# Main_Board.net
KiCad netlist of a schematic drawn in EAGLE
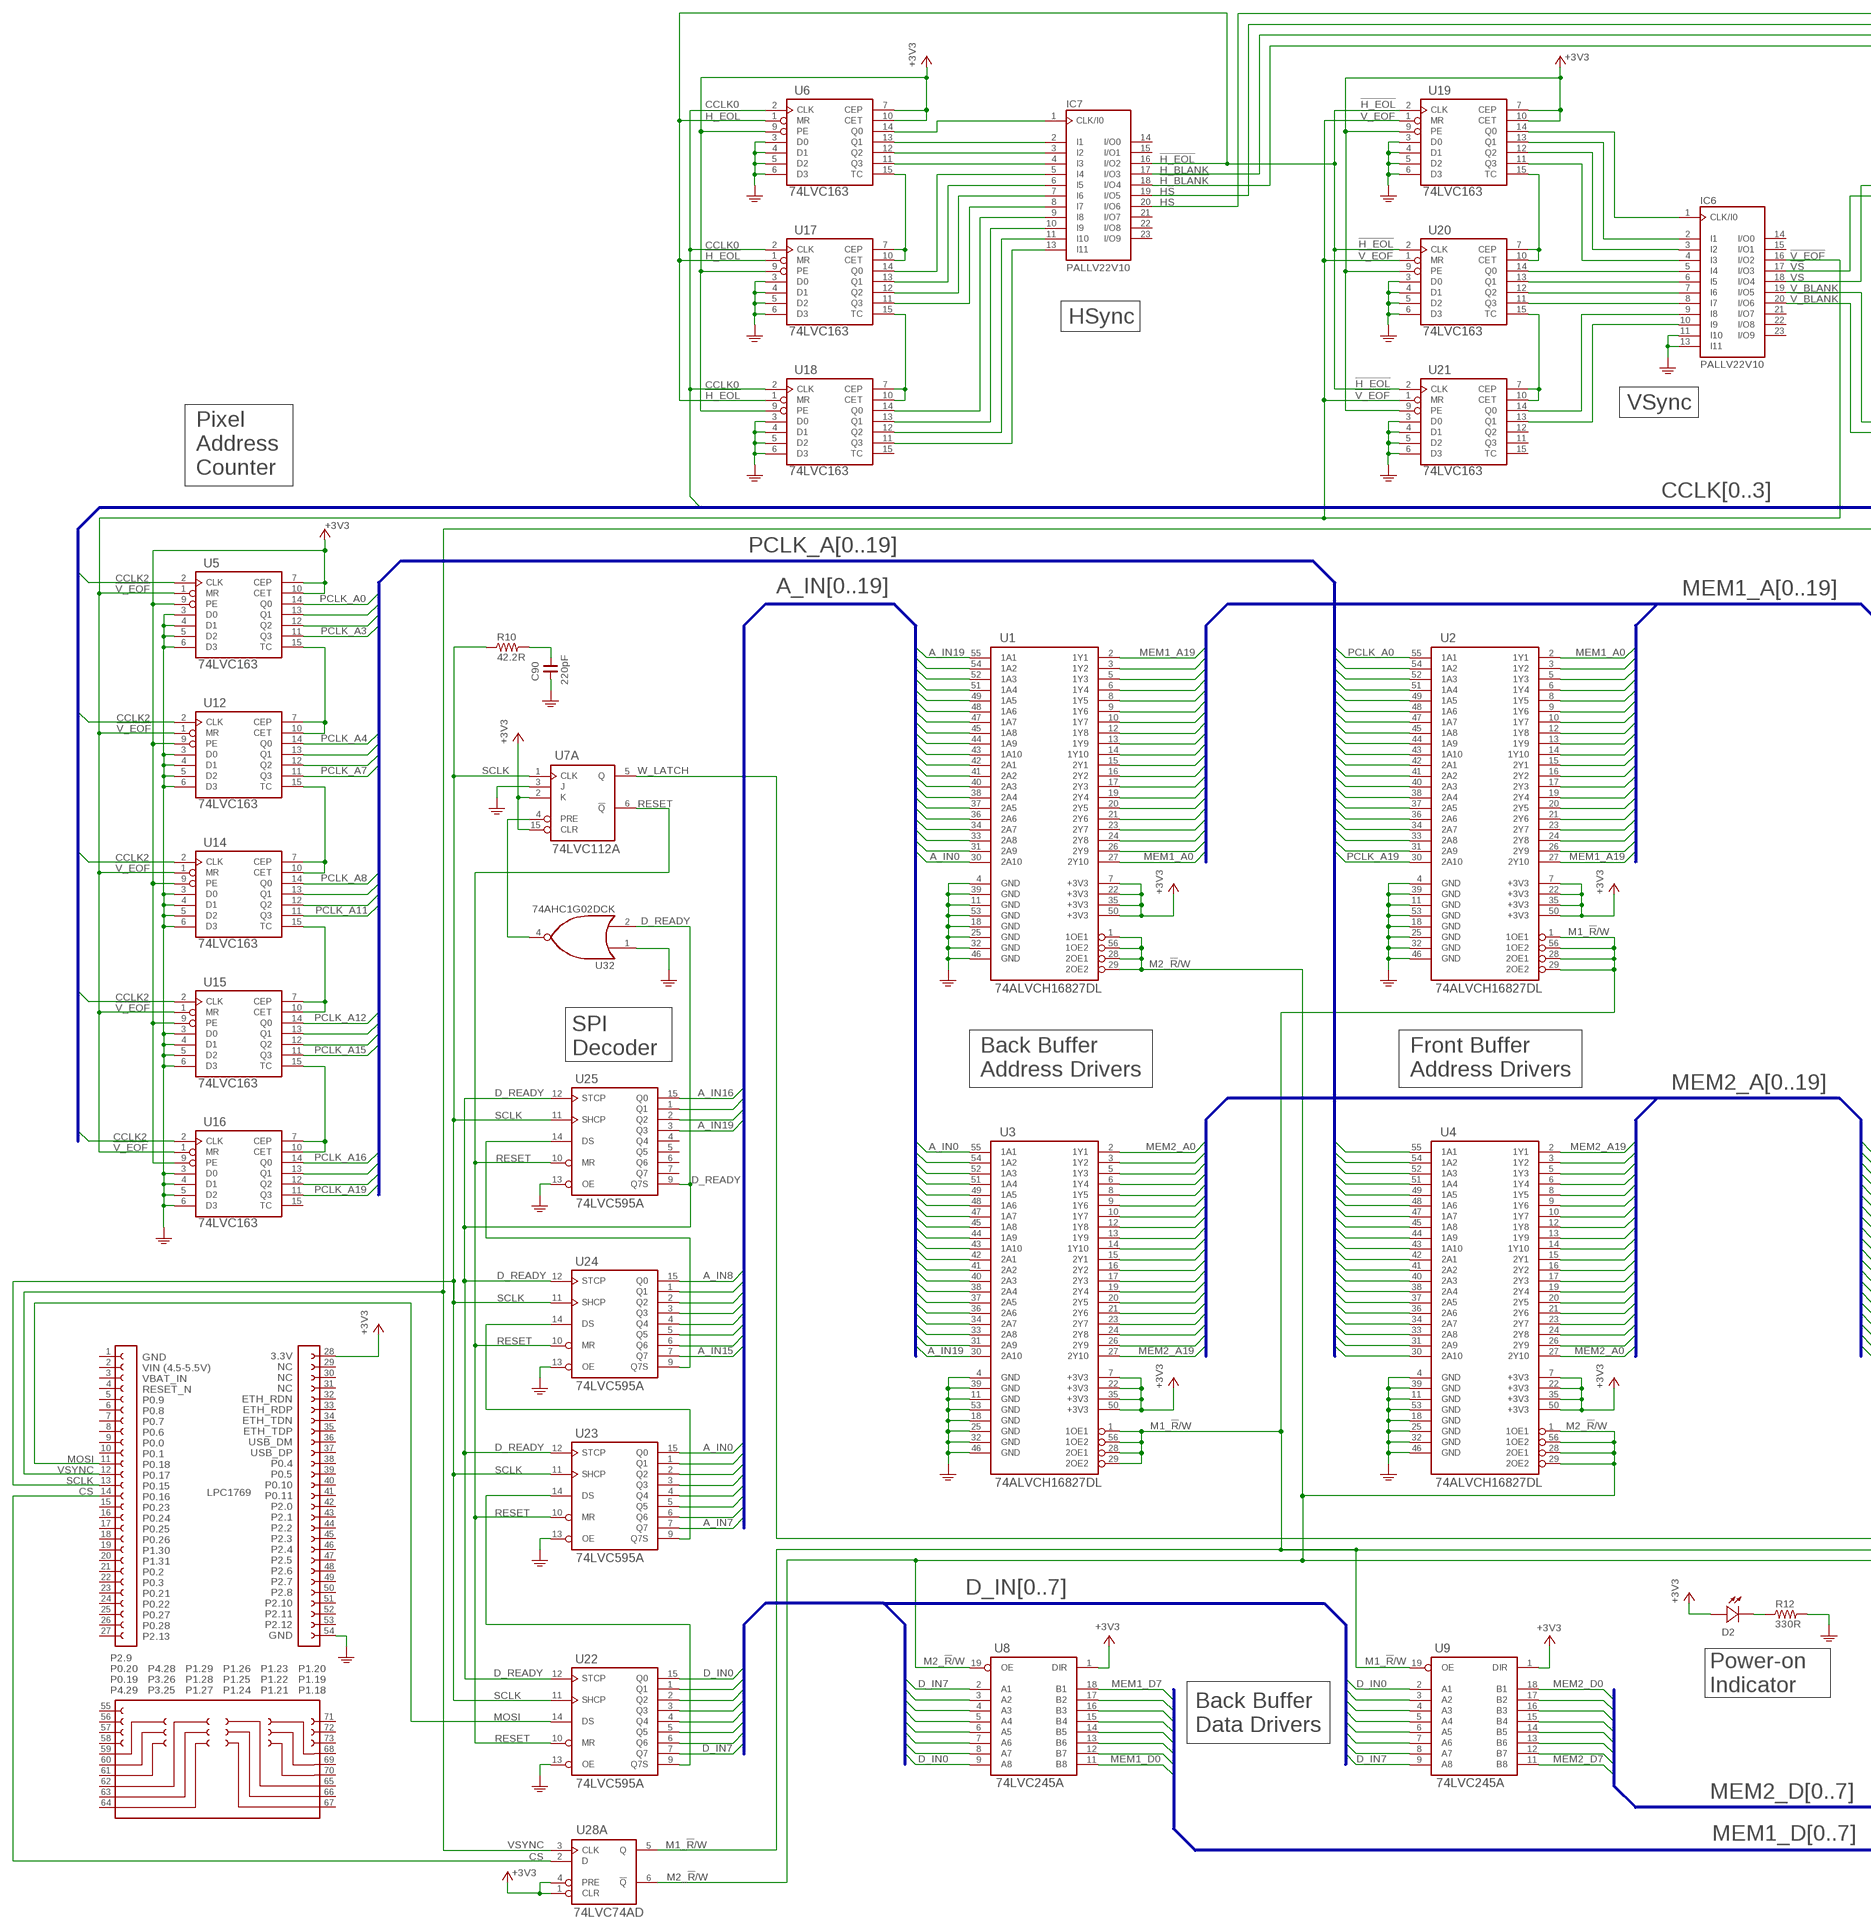
[diagram p0: schematic, sheet 1, part 1 of 2]
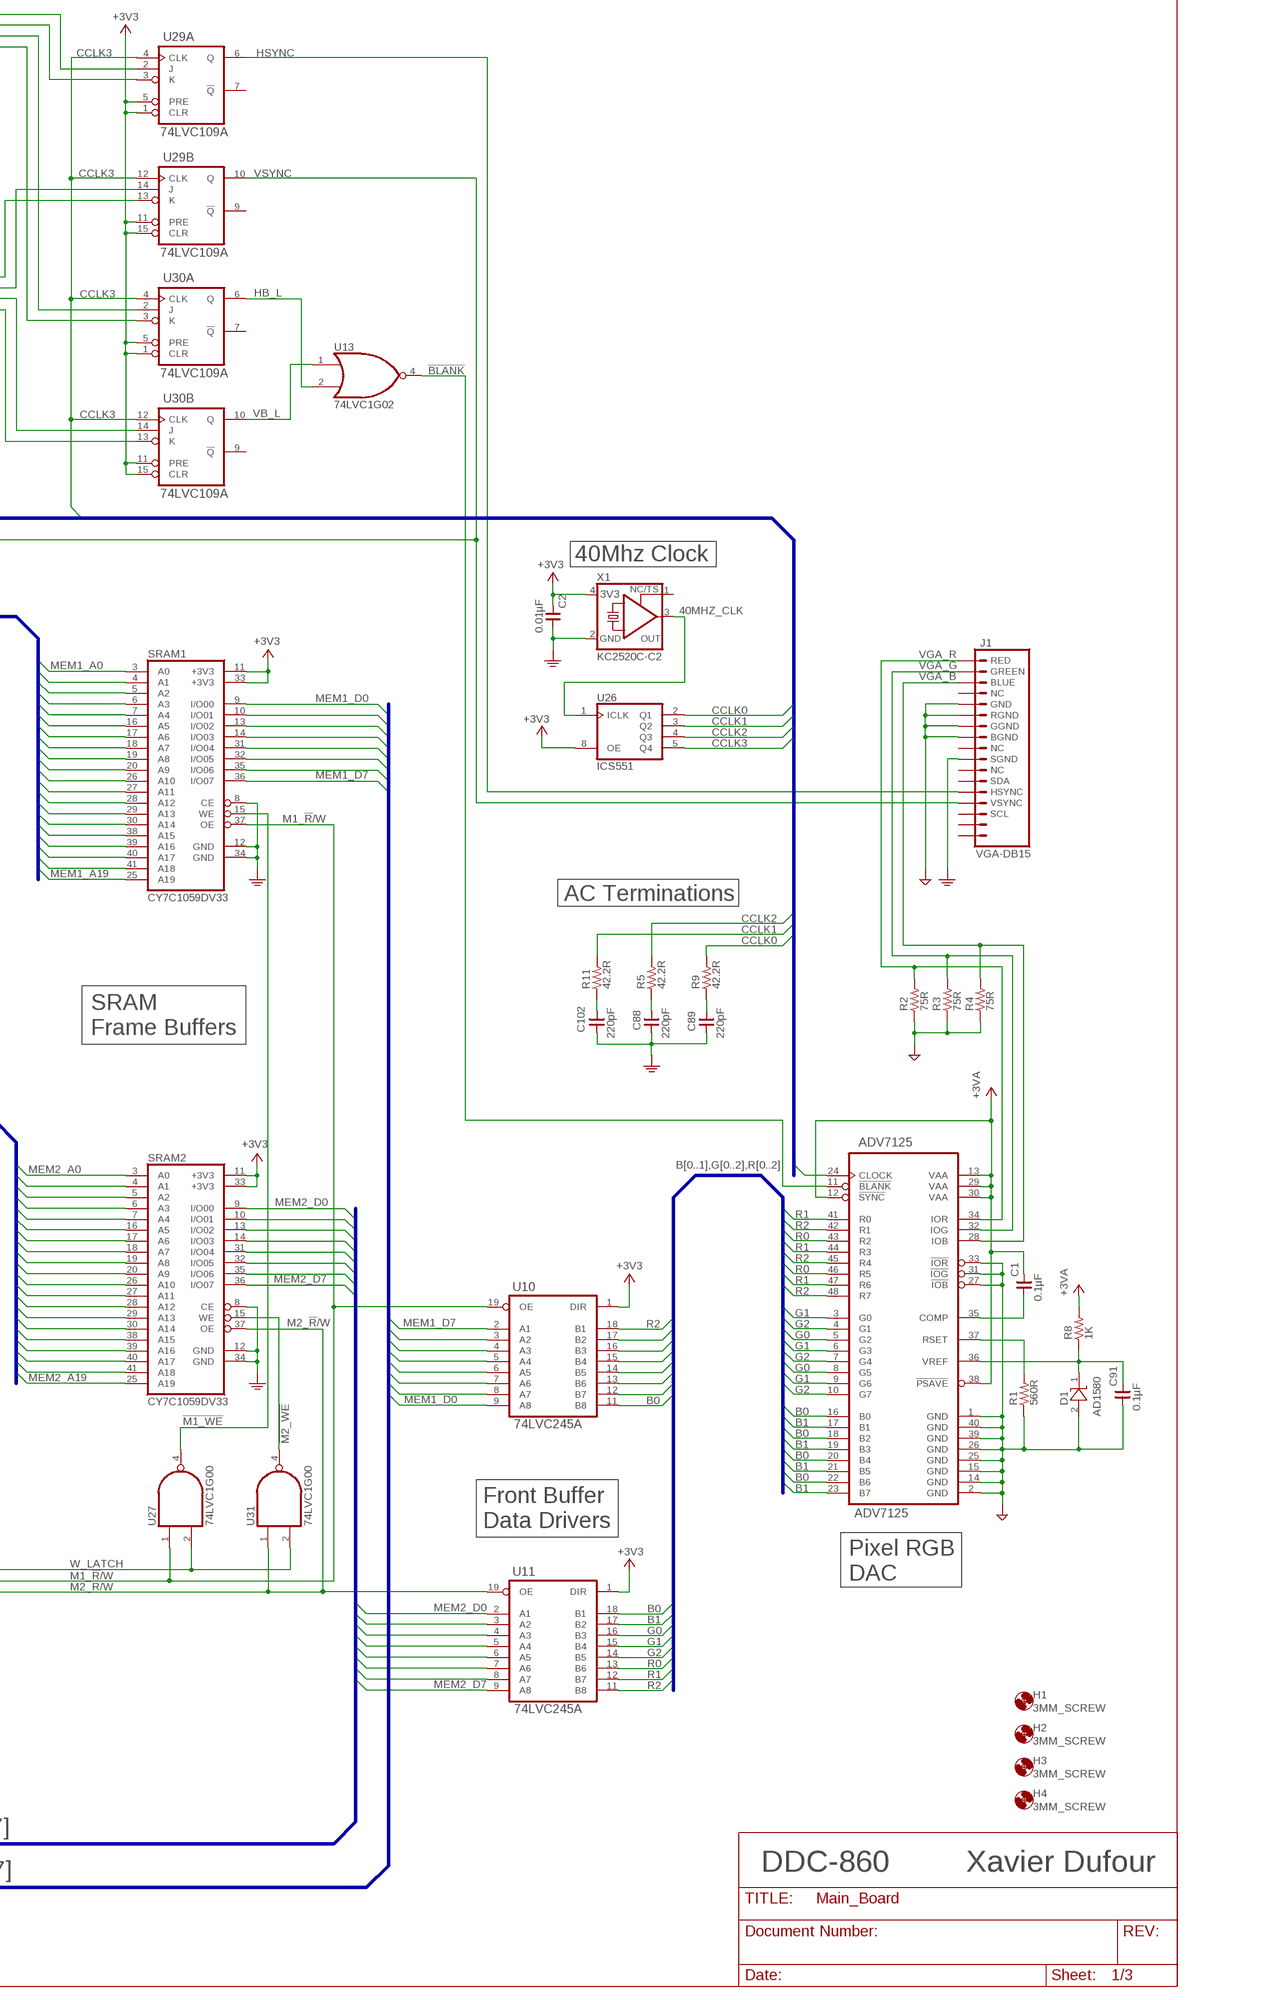
[diagram p1: schematic, sheet 1, part 2 of 2]
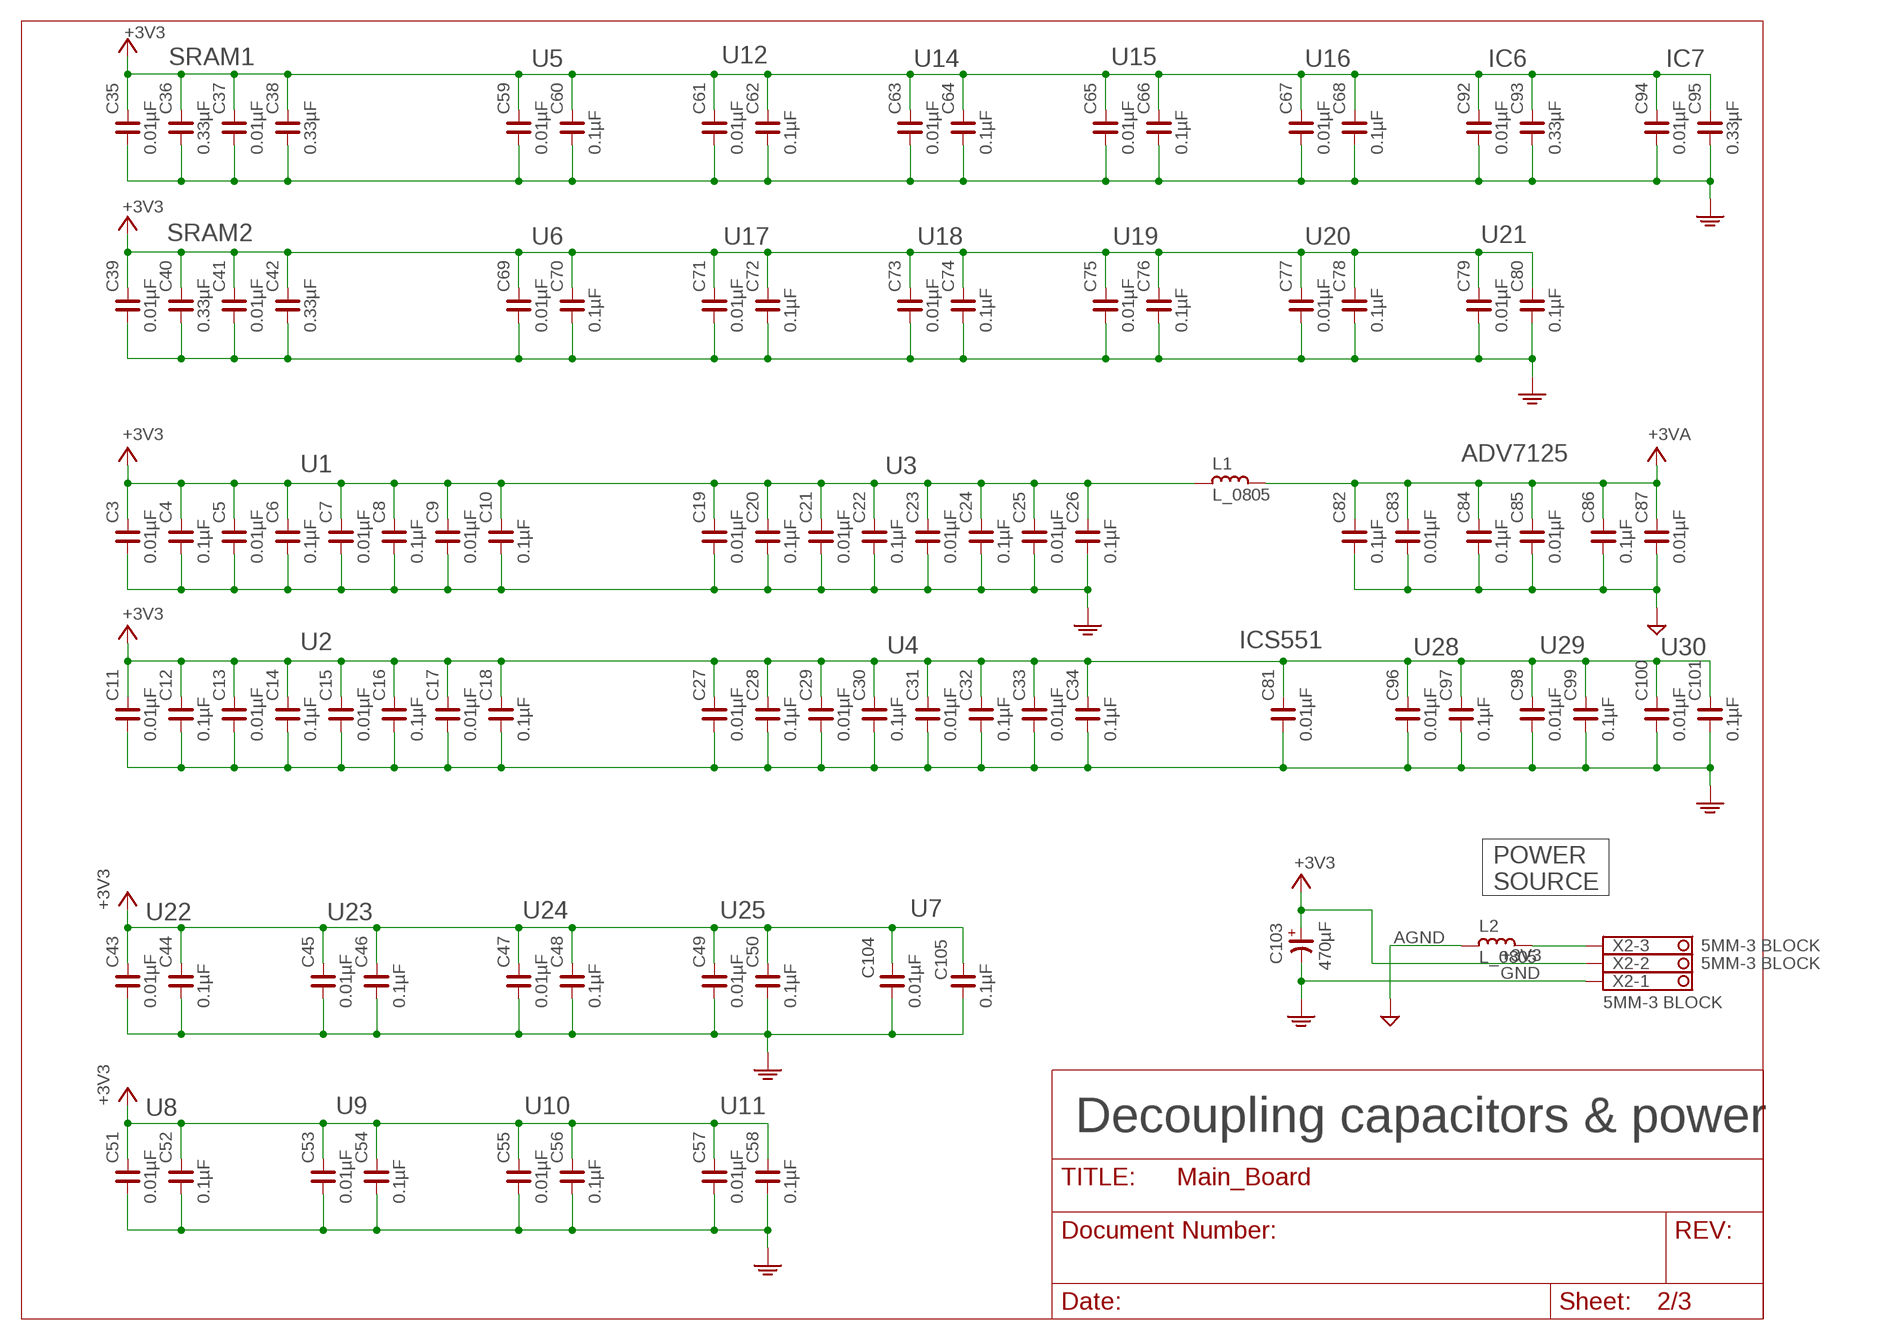
[diagram p2: schematic, sheet 2]
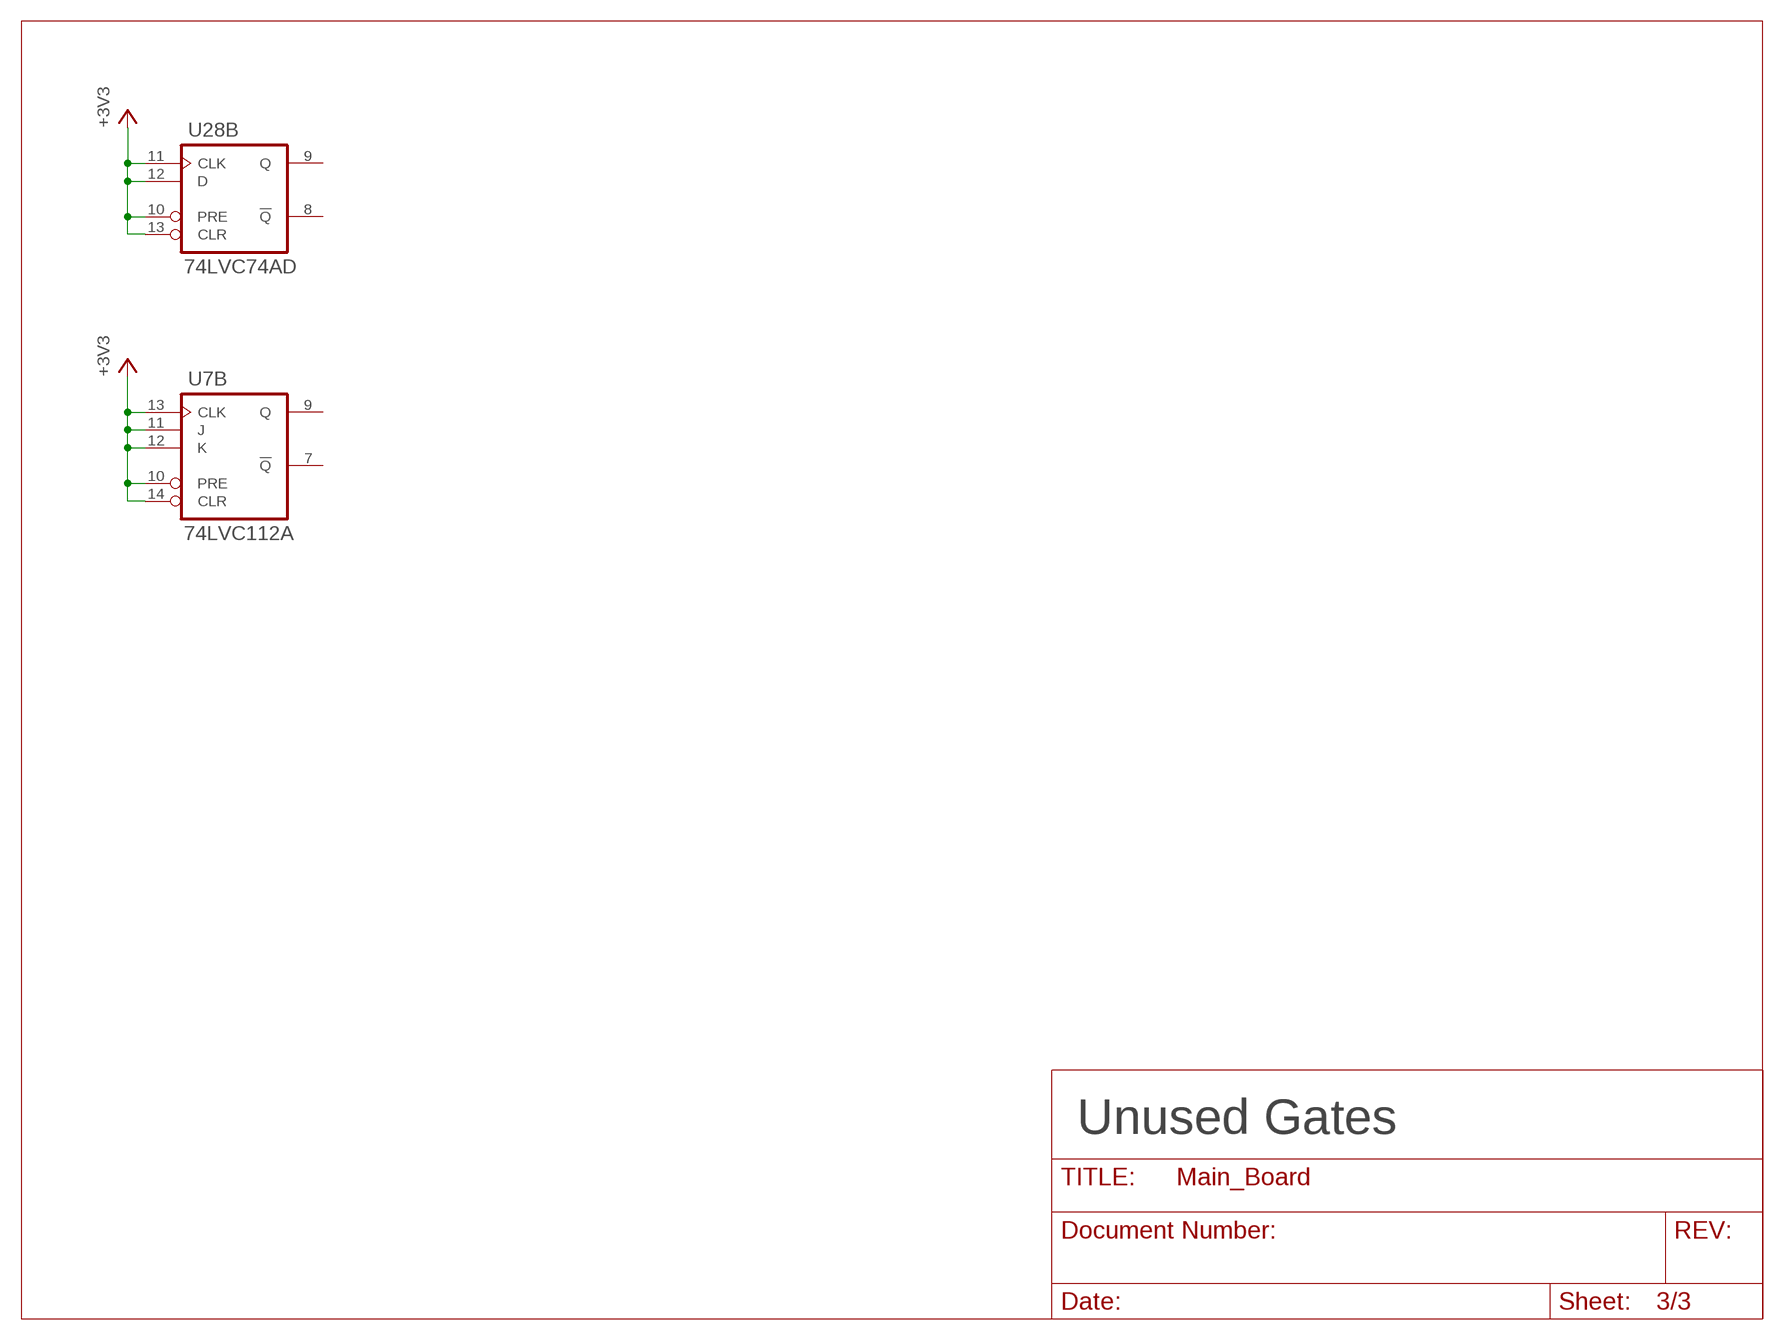
[diagram p3: schematic, sheet 3]

(export (version "E")
  (design (tool "Eeschema 10.0.6"))
  (components
    (comp (ref "C3")
      (value "0.01µF")
      (footprint "eagle-import:C0603")
      (libsource (lib "eagle-import") (part "C_0603"))
    )
    (comp (ref "C4")
      (value "0.1µF")
      (footprint "eagle-import:C0603")
      (libsource (lib "eagle-import") (part "C_0603"))
    )
    (comp (ref "C5")
      (value "0.01µF")
      (footprint "eagle-import:C0603")
      (libsource (lib "eagle-import") (part "C_0603"))
    )
    (comp (ref "C6")
      (value "0.1µF")
      (footprint "eagle-import:C0603")
      (libsource (lib "eagle-import") (part "C_0603"))
    )
    (comp (ref "C7")
      (value "0.01µF")
      (footprint "eagle-import:C0603")
      (libsource (lib "eagle-import") (part "C_0603"))
    )
    (comp (ref "C8")
      (value "0.1µF")
      (footprint "eagle-import:C0603")
      (libsource (lib "eagle-import") (part "C_0603"))
    )
    (comp (ref "C9")
      (value "0.01µF")
      (footprint "eagle-import:C0603")
      (libsource (lib "eagle-import") (part "C_0603"))
    )
    (comp (ref "C10")
      (value "0.1µF")
      (footprint "eagle-import:C0603")
      (libsource (lib "eagle-import") (part "C_0603"))
    )
    (comp (ref "C11")
      (value "0.01µF")
      (footprint "eagle-import:C0603")
      (libsource (lib "eagle-import") (part "C_0603"))
    )
    (comp (ref "C12")
      (value "0.1µF")
      (footprint "eagle-import:C0603")
      (libsource (lib "eagle-import") (part "C_0603"))
    )
    (comp (ref "C13")
      (value "0.01µF")
      (footprint "eagle-import:C0603")
      (libsource (lib "eagle-import") (part "C_0603"))
    )
    (comp (ref "C14")
      (value "0.1µF")
      (footprint "eagle-import:C0603")
      (libsource (lib "eagle-import") (part "C_0603"))
    )
    (comp (ref "C15")
      (value "0.01µF")
      (footprint "eagle-import:C0603")
      (libsource (lib "eagle-import") (part "C_0603"))
    )
    (comp (ref "C16")
      (value "0.1µF")
      (footprint "eagle-import:C0603")
      (libsource (lib "eagle-import") (part "C_0603"))
    )
    (comp (ref "C17")
      (value "0.01µF")
      (footprint "eagle-import:C0603")
      (libsource (lib "eagle-import") (part "C_0603"))
    )
    (comp (ref "C18")
      (value "0.1µF")
      (footprint "eagle-import:C0603")
      (libsource (lib "eagle-import") (part "C_0603"))
    )
    (comp (ref "C19")
      (value "0.01µF")
      (footprint "eagle-import:C0603")
      (libsource (lib "eagle-import") (part "C_0603"))
    )
    (comp (ref "C20")
      (value "0.1µF")
      (footprint "eagle-import:C0603")
      (libsource (lib "eagle-import") (part "C_0603"))
    )
    (comp (ref "C21")
      (value "0.01µF")
      (footprint "eagle-import:C0603")
      (libsource (lib "eagle-import") (part "C_0603"))
    )
    (comp (ref "C22")
      (value "0.1µF")
      (footprint "eagle-import:C0603")
      (libsource (lib "eagle-import") (part "C_0603"))
    )
    (comp (ref "C23")
      (value "0.01µF")
      (footprint "eagle-import:C0603")
      (libsource (lib "eagle-import") (part "C_0603"))
    )
    (comp (ref "C24")
      (value "0.1µF")
      (footprint "eagle-import:C0603")
      (libsource (lib "eagle-import") (part "C_0603"))
    )
    (comp (ref "C25")
      (value "0.01µF")
      (footprint "eagle-import:C0603")
      (libsource (lib "eagle-import") (part "C_0603"))
    )
    (comp (ref "C26")
      (value "0.1µF")
      (footprint "eagle-import:C0603")
      (libsource (lib "eagle-import") (part "C_0603"))
    )
    (comp (ref "C27")
      (value "0.01µF")
      (footprint "eagle-import:C0603")
      (libsource (lib "eagle-import") (part "C_0603"))
    )
    (comp (ref "C28")
      (value "0.1µF")
      (footprint "eagle-import:C0603")
      (libsource (lib "eagle-import") (part "C_0603"))
    )
    (comp (ref "C29")
      (value "0.01µF")
      (footprint "eagle-import:C0603")
      (libsource (lib "eagle-import") (part "C_0603"))
    )
    (comp (ref "C30")
      (value "0.1µF")
      (footprint "eagle-import:C0603")
      (libsource (lib "eagle-import") (part "C_0603"))
    )
    (comp (ref "C31")
      (value "0.01µF")
      (footprint "eagle-import:C0603")
      (libsource (lib "eagle-import") (part "C_0603"))
    )
    (comp (ref "C32")
      (value "0.1µF")
      (footprint "eagle-import:C0603")
      (libsource (lib "eagle-import") (part "C_0603"))
    )
    (comp (ref "C33")
      (value "0.01µF")
      (footprint "eagle-import:C0603")
      (libsource (lib "eagle-import") (part "C_0603"))
    )
    (comp (ref "C34")
      (value "0.1µF")
      (footprint "eagle-import:C0603")
      (libsource (lib "eagle-import") (part "C_0603"))
    )
    (comp (ref "C35")
      (value "0.01µF")
      (footprint "eagle-import:C0603")
      (libsource (lib "eagle-import") (part "C_0603"))
    )
    (comp (ref "C36")
      (value "0.33µF")
      (footprint "eagle-import:C0603")
      (libsource (lib "eagle-import") (part "C_0603"))
    )
    (comp (ref "C37")
      (value "0.01µF")
      (footprint "eagle-import:C0603")
      (libsource (lib "eagle-import") (part "C_0603"))
    )
    (comp (ref "C38")
      (value "0.33µF")
      (footprint "eagle-import:C0603")
      (libsource (lib "eagle-import") (part "C_0603"))
    )
    (comp (ref "C39")
      (value "0.01µF")
      (footprint "eagle-import:C0603")
      (libsource (lib "eagle-import") (part "C_0603"))
    )
    (comp (ref "C40")
      (value "0.33µF")
      (footprint "eagle-import:C0603")
      (libsource (lib "eagle-import") (part "C_0603"))
    )
    (comp (ref "C41")
      (value "0.01µF")
      (footprint "eagle-import:C0603")
      (libsource (lib "eagle-import") (part "C_0603"))
    )
    (comp (ref "C42")
      (value "0.33µF")
      (footprint "eagle-import:C0603")
      (libsource (lib "eagle-import") (part "C_0603"))
    )
    (comp (ref "C43")
      (value "0.01µF")
      (footprint "eagle-import:C0603")
      (libsource (lib "eagle-import") (part "C_0603"))
    )
    (comp (ref "C44")
      (value "0.1µF")
      (footprint "eagle-import:C0603")
      (libsource (lib "eagle-import") (part "C_0603"))
    )
    (comp (ref "C45")
      (value "0.01µF")
      (footprint "eagle-import:C0603")
      (libsource (lib "eagle-import") (part "C_0603"))
    )
    (comp (ref "C46")
      (value "0.1µF")
      (footprint "eagle-import:C0603")
      (libsource (lib "eagle-import") (part "C_0603"))
    )
    (comp (ref "C47")
      (value "0.01µF")
      (footprint "eagle-import:C0603")
      (fields (field (name "SPICEPREFIX") "C"))
      (libsource (lib "eagle-import") (part "C_0603"))
    )
    (comp (ref "C48")
      (value "0.1µF")
      (footprint "eagle-import:C0603")
      (libsource (lib "eagle-import") (part "C_0603"))
    )
    (comp (ref "C49")
      (value "0.01µF")
      (footprint "eagle-import:C0603")
      (libsource (lib "eagle-import") (part "C_0603"))
    )
    (comp (ref "C50")
      (value "0.1µF")
      (footprint "eagle-import:C0603")
      (libsource (lib "eagle-import") (part "C_0603"))
    )
    (comp (ref "C51")
      (value "0.01µF")
      (footprint "eagle-import:C0603")
      (libsource (lib "eagle-import") (part "C_0603"))
    )
    (comp (ref "C52")
      (value "0.1µF")
      (footprint "eagle-import:C0603")
      (libsource (lib "eagle-import") (part "C_0603"))
    )
    (comp (ref "C53")
      (value "0.01µF")
      (footprint "eagle-import:C0603")
      (libsource (lib "eagle-import") (part "C_0603"))
    )
    (comp (ref "C54")
      (value "0.1µF")
      (footprint "eagle-import:C0603")
      (libsource (lib "eagle-import") (part "C_0603"))
    )
    (comp (ref "C55")
      (value "0.01µF")
      (footprint "eagle-import:C0603")
      (libsource (lib "eagle-import") (part "C_0603"))
    )
    (comp (ref "C56")
      (value "0.1µF")
      (footprint "eagle-import:C0603")
      (libsource (lib "eagle-import") (part "C_0603"))
    )
    (comp (ref "C57")
      (value "0.01µF")
      (footprint "eagle-import:C0603")
      (libsource (lib "eagle-import") (part "C_0603"))
    )
    (comp (ref "C58")
      (value "0.1µF")
      (footprint "eagle-import:C0603")
      (libsource (lib "eagle-import") (part "C_0603"))
    )
    (comp (ref "C59")
      (value "0.01µF")
      (footprint "eagle-import:C0603")
      (libsource (lib "eagle-import") (part "C_0603"))
    )
    (comp (ref "C60")
      (value "0.1µF")
      (footprint "eagle-import:C0603")
      (libsource (lib "eagle-import") (part "C_0603"))
    )
    (comp (ref "C61")
      (value "0.01µF")
      (footprint "eagle-import:C0603")
      (libsource (lib "eagle-import") (part "C_0603"))
    )
    (comp (ref "C62")
      (value "0.1µF")
      (footprint "eagle-import:C0603")
      (libsource (lib "eagle-import") (part "C_0603"))
    )
    (comp (ref "C63")
      (value "0.01µF")
      (footprint "eagle-import:C0603")
      (libsource (lib "eagle-import") (part "C_0603"))
    )
    (comp (ref "C64")
      (value "0.1µF")
      (footprint "eagle-import:C0603")
      (libsource (lib "eagle-import") (part "C_0603"))
    )
    (comp (ref "C65")
      (value "0.01µF")
      (footprint "eagle-import:C0603")
      (libsource (lib "eagle-import") (part "C_0603"))
    )
    (comp (ref "C66")
      (value "0.1µF")
      (footprint "eagle-import:C0603")
      (libsource (lib "eagle-import") (part "C_0603"))
    )
    (comp (ref "C67")
      (value "0.01µF")
      (footprint "eagle-import:C0603")
      (libsource (lib "eagle-import") (part "C_0603"))
    )
    (comp (ref "C68")
      (value "0.1µF")
      (footprint "eagle-import:C0603")
      (libsource (lib "eagle-import") (part "C_0603"))
    )
    (comp (ref "C69")
      (value "0.01µF")
      (footprint "eagle-import:C0603")
      (libsource (lib "eagle-import") (part "C_0603"))
    )
    (comp (ref "C70")
      (value "0.1µF")
      (footprint "eagle-import:C0603")
      (libsource (lib "eagle-import") (part "C_0603"))
    )
    (comp (ref "C71")
      (value "0.01µF")
      (footprint "eagle-import:C0603")
      (libsource (lib "eagle-import") (part "C_0603"))
    )
    (comp (ref "C72")
      (value "0.1µF")
      (footprint "eagle-import:C0603")
      (libsource (lib "eagle-import") (part "C_0603"))
    )
    (comp (ref "C73")
      (value "0.01µF")
      (footprint "eagle-import:C0603")
      (libsource (lib "eagle-import") (part "C_0603"))
    )
    (comp (ref "C74")
      (value "0.1µF")
      (footprint "eagle-import:C0603")
      (libsource (lib "eagle-import") (part "C_0603"))
    )
    (comp (ref "C75")
      (value "0.01µF")
      (footprint "eagle-import:C0603")
      (libsource (lib "eagle-import") (part "C_0603"))
    )
    (comp (ref "C76")
      (value "0.1µF")
      (footprint "eagle-import:C0603")
      (libsource (lib "eagle-import") (part "C_0603"))
    )
    (comp (ref "C77")
      (value "0.01µF")
      (footprint "eagle-import:C0603")
      (libsource (lib "eagle-import") (part "C_0603"))
    )
    (comp (ref "C78")
      (value "0.1µF")
      (footprint "eagle-import:C0603")
      (libsource (lib "eagle-import") (part "C_0603"))
    )
    (comp (ref "C79")
      (value "0.01µF")
      (footprint "eagle-import:C0603")
      (libsource (lib "eagle-import") (part "C_0603"))
    )
    (comp (ref "C80")
      (value "0.1µF")
      (footprint "eagle-import:C0603")
      (libsource (lib "eagle-import") (part "C_0603"))
    )
    (comp (ref "C81")
      (value "0.01µF")
      (footprint "eagle-import:C0603")
      (libsource (lib "eagle-import") (part "C_0603"))
    )
    (comp (ref "C82")
      (value "0.1µF")
      (footprint "eagle-import:C0603")
      (libsource (lib "eagle-import") (part "C_0603"))
    )
    (comp (ref "C83")
      (value "0.01µF")
      (footprint "eagle-import:C0603")
      (libsource (lib "eagle-import") (part "C_0603"))
    )
    (comp (ref "C84")
      (value "0.1µF")
      (footprint "eagle-import:C0603")
      (libsource (lib "eagle-import") (part "C_0603"))
    )
    (comp (ref "C85")
      (value "0.01µF")
      (footprint "eagle-import:C0603")
      (libsource (lib "eagle-import") (part "C_0603"))
    )
    (comp (ref "C86")
      (value "0.1µF")
      (footprint "eagle-import:C0603")
      (libsource (lib "eagle-import") (part "C_0603"))
    )
    (comp (ref "C87")
      (value "0.01µF")
      (footprint "eagle-import:C0603")
      (libsource (lib "eagle-import") (part "C_0603"))
    )
    (comp (ref "C92")
      (value "0.01µF")
      (footprint "eagle-import:C0603")
      (libsource (lib "eagle-import") (part "C_0603"))
    )
    (comp (ref "C93")
      (value "0.33µF")
      (footprint "eagle-import:C0603")
      (libsource (lib "eagle-import") (part "C_0603"))
    )
    (comp (ref "C94")
      (value "0.01µF")
      (footprint "eagle-import:C0603")
      (libsource (lib "eagle-import") (part "C_0603"))
    )
    (comp (ref "C95")
      (value "0.33µF")
      (footprint "eagle-import:C0603")
      (libsource (lib "eagle-import") (part "C_0603"))
    )
    (comp (ref "C96")
      (value "0.01µF")
      (footprint "eagle-import:C0603")
      (libsource (lib "eagle-import") (part "C_0603"))
    )
    (comp (ref "C97")
      (value "0.1µF")
      (footprint "eagle-import:C0603")
      (libsource (lib "eagle-import") (part "C_0603"))
    )
    (comp (ref "C98")
      (value "0.01µF")
      (footprint "eagle-import:C0603")
      (libsource (lib "eagle-import") (part "C_0603"))
    )
    (comp (ref "C99")
      (value "0.1µF")
      (footprint "eagle-import:C0603")
      (libsource (lib "eagle-import") (part "C_0603"))
    )
    (comp (ref "C100")
      (value "0.01µF")
      (footprint "eagle-import:C0603")
      (libsource (lib "eagle-import") (part "C_0603"))
    )
    (comp (ref "C101")
      (value "0.1µF")
      (footprint "eagle-import:C0603")
      (libsource (lib "eagle-import") (part "C_0603"))
    )
    (comp (ref "C103")
      (value "470µF")
      (footprint "eagle-import:CSV-G")
      (libsource (lib "eagle-import") (part "CP_SV-G"))
    )
    (comp (ref "C104")
      (value "0.01µF")
      (footprint "eagle-import:C0603")
      (libsource (lib "eagle-import") (part "C_0603"))
    )
    (comp (ref "C105")
      (value "0.1µF")
      (footprint "eagle-import:C0603")
      (libsource (lib "eagle-import") (part "C_0603"))
    )
    (comp (ref "L1")
      (value "L_0805")
      (footprint "eagle-import:L0805")
      (libsource (lib "eagle-import") (part "L_0805"))
    )
    (comp (ref "L2")
      (value "L_0805")
      (footprint "eagle-import:L0805")
      (libsource (lib "eagle-import") (part "L_0805"))
    )
    (comp (ref "X2")
      (value "5MM-3 BLOCK")
      (footprint "eagle-import:TERMINAL-BLOCK-3-PIN-5MM")
      (libsource (lib "eagle-import") (part "TERMINAL-BLOCK-5MM-3-PIN-LONG-PAD"))
    )
    (comp (ref "U7")
      (value "74LVC112A")
      (footprint "eagle-import:SO16D(SOT109)")
      (libsource (lib "eagle-import") (part "74LVC112A"))
    )
    (comp (ref "U28")
      (value "74LVC74AD")
      (footprint "eagle-import:SO14(SOT108)")
      (libsource (lib "eagle-import") (part "74LVC74AD"))
    )
    (comp (ref "ADV7125")
      (value "ADV7125")
      (footprint "eagle-import:LQFP48(SOT313)")
      (libsource (lib "eagle-import") (part "ADV7125"))
    )
    (comp (ref "C1")
      (value "0.1µF")
      (footprint "eagle-import:C0603")
      (libsource (lib "eagle-import") (part "C_0603"))
    )
    (comp (ref "C2")
      (value "0.01µF")
      (footprint "eagle-import:C0603")
      (libsource (lib "eagle-import") (part "C_0603"))
    )
    (comp (ref "C88")
      (value "220pF")
      (footprint "eagle-import:C0603")
      (libsource (lib "eagle-import") (part "C_0603"))
    )
    (comp (ref "C89")
      (value "220pF")
      (footprint "eagle-import:C0603")
      (libsource (lib "eagle-import") (part "C_0603"))
    )
    (comp (ref "C90")
      (value "220pF")
      (footprint "eagle-import:C0603")
      (libsource (lib "eagle-import") (part "C_0603"))
    )
    (comp (ref "C91")
      (value "0.1µF")
      (footprint "eagle-import:C0603")
      (libsource (lib "eagle-import") (part "C_0603"))
    )
    (comp (ref "C102")
      (value "220pF")
      (footprint "eagle-import:C0603")
      (libsource (lib "eagle-import") (part "C_0603"))
    )
    (comp (ref "D1")
      (value "AD1580")
      (footprint "eagle-import:TO236-3(SOT23)")
      (fields (field (name "MPN") "AD1580BRTZ"))
      (libsource (lib "eagle-import") (part "AD1580"))
    )
    (comp (ref "D2")
      (value "DEL-1206")
      (footprint "eagle-import:DEL1206")
      (libsource (lib "eagle-import") (part "DEL-1206"))
    )
    (comp (ref "H1")
      (value "3MM_SCREW")
      (footprint "eagle-import:3MM_HOLE")
      (libsource (lib "eagle-import") (part "SCREW_MOUNT_HOLE3.0"))
    )
    (comp (ref "H2")
      (value "3MM_SCREW")
      (footprint "eagle-import:3MM_HOLE")
      (libsource (lib "eagle-import") (part "SCREW_MOUNT_HOLE3.0"))
    )
    (comp (ref "H3")
      (value "3MM_SCREW")
      (footprint "eagle-import:3MM_HOLE")
      (libsource (lib "eagle-import") (part "SCREW_MOUNT_HOLE3.0"))
    )
    (comp (ref "H4")
      (value "3MM_SCREW")
      (footprint "eagle-import:3MM_HOLE")
      (libsource (lib "eagle-import") (part "SCREW_MOUNT_HOLE3.0"))
    )
    (comp (ref "IC6")
      (value "PALLV22V10")
      (footprint "eagle-import:DIP24")
      (libsource (lib "eagle-import") (part "PALLV22V10"))
    )
    (comp (ref "IC7")
      (value "PALLV22V10")
      (footprint "eagle-import:DIP24")
      (libsource (lib "eagle-import") (part "PALLV22V10"))
    )
    (comp (ref "J1")
      (value "VGA-DB15")
      (footprint "eagle-import:DB15-VGA-90DEG")
      (libsource (lib "eagle-import") (part "VGA-DB15"))
    )
    (comp (ref "LPC1769")
      (value "LPCXPRESSO_LPC1769")
      (footprint "eagle-import:LPCXPRESSO_LPC1769")
      (libsource (lib "eagle-import") (part "LPCXPRESSO_LPC1769"))
    )
    (comp (ref "R1")
      (value "560R")
      (footprint "eagle-import:R0603")
      (libsource (lib "eagle-import") (part "R_0603"))
    )
    (comp (ref "R2")
      (value "75R")
      (footprint "eagle-import:R0603")
      (libsource (lib "eagle-import") (part "R_0603"))
    )
    (comp (ref "R3")
      (value "75R")
      (footprint "eagle-import:R0603")
      (libsource (lib "eagle-import") (part "R_0603"))
    )
    (comp (ref "R4")
      (value "75R")
      (footprint "eagle-import:R0603")
      (libsource (lib "eagle-import") (part "R_0603"))
    )
    (comp (ref "R5")
      (value "42.2R")
      (footprint "eagle-import:R0603")
      (libsource (lib "eagle-import") (part "R_0603"))
    )
    (comp (ref "R8")
      (value "1K")
      (footprint "eagle-import:R0603")
      (libsource (lib "eagle-import") (part "R_0603"))
    )
    (comp (ref "R9")
      (value "42.2R")
      (footprint "eagle-import:R0603")
      (libsource (lib "eagle-import") (part "R_0603"))
    )
    (comp (ref "R10")
      (value "42.2R")
      (footprint "eagle-import:R0603")
      (libsource (lib "eagle-import") (part "R_0603"))
    )
    (comp (ref "R11")
      (value "42.2R")
      (footprint "eagle-import:R0603")
      (libsource (lib "eagle-import") (part "R_0603"))
    )
    (comp (ref "R12")
      (value "330R")
      (footprint "eagle-import:R1206")
      (libsource (lib "eagle-import") (part "R_1206"))
    )
    (comp (ref "SRAM1")
      (value "CY7C1059DV33")
      (footprint "eagle-import:TSOPII-44")
      (libsource (lib "eagle-import") (part "CY7C1059DV33"))
    )
    (comp (ref "SRAM2")
      (value "CY7C1059DV33")
      (footprint "eagle-import:TSOPII-44")
      (libsource (lib "eagle-import") (part "CY7C1059DV33"))
    )
    (comp (ref "U1")
      (value "74ALVCH16827DL")
      (footprint "eagle-import:SSOP56(SOT371)")
      (libsource (lib "eagle-import") (part "74ALVCH16827DL"))
    )
    (comp (ref "U2")
      (value "74ALVCH16827DL")
      (footprint "eagle-import:SSOP56(SOT371)")
      (libsource (lib "eagle-import") (part "74ALVCH16827DL"))
    )
    (comp (ref "U3")
      (value "74ALVCH16827DL")
      (footprint "eagle-import:SSOP56(SOT371)")
      (libsource (lib "eagle-import") (part "74ALVCH16827DL"))
    )
    (comp (ref "U4")
      (value "74ALVCH16827DL")
      (footprint "eagle-import:SSOP56(SOT371)")
      (libsource (lib "eagle-import") (part "74ALVCH16827DL"))
    )
    (comp (ref "U5")
      (value "74LVC163")
      (footprint "eagle-import:SO16D(SOT109)")
      (libsource (lib "eagle-import") (part "74LVC163"))
    )
    (comp (ref "U6")
      (value "74LVC163")
      (footprint "eagle-import:SO16D(SOT109)")
      (libsource (lib "eagle-import") (part "74LVC163"))
    )
    (comp (ref "U8")
      (value "74LVC245A")
      (footprint "eagle-import:SO20DW(SOT163)")
      (libsource (lib "eagle-import") (part "74LVC245A"))
    )
    (comp (ref "U9")
      (value "74LVC245A")
      (footprint "eagle-import:SO20DW(SOT163)")
      (libsource (lib "eagle-import") (part "74LVC245A"))
    )
    (comp (ref "U10")
      (value "74LVC245A")
      (footprint "eagle-import:SO20DW(SOT163)")
      (libsource (lib "eagle-import") (part "74LVC245A"))
    )
    (comp (ref "U11")
      (value "74LVC245A")
      (footprint "eagle-import:SO20DW(SOT163)")
      (libsource (lib "eagle-import") (part "74LVC245A"))
    )
    (comp (ref "U12")
      (value "74LVC163")
      (footprint "eagle-import:SO16D(SOT109)")
      (libsource (lib "eagle-import") (part "74LVC163"))
    )
    (comp (ref "U13")
      (value "74LVC1G02")
      (footprint "eagle-import:SC70-5(SOT353)")
      (libsource (lib "eagle-import") (part "74LVC1G02"))
    )
    (comp (ref "U14")
      (value "74LVC163")
      (footprint "eagle-import:SO16D(SOT109)")
      (libsource (lib "eagle-import") (part "74LVC163"))
    )
    (comp (ref "U15")
      (value "74LVC163")
      (footprint "eagle-import:SO16D(SOT109)")
      (libsource (lib "eagle-import") (part "74LVC163"))
    )
    (comp (ref "U16")
      (value "74LVC163")
      (footprint "eagle-import:SO16D(SOT109)")
      (libsource (lib "eagle-import") (part "74LVC163"))
    )
    (comp (ref "U17")
      (value "74LVC163")
      (footprint "eagle-import:SO16D(SOT109)")
      (libsource (lib "eagle-import") (part "74LVC163"))
    )
    (comp (ref "U18")
      (value "74LVC163")
      (footprint "eagle-import:SO16D(SOT109)")
      (libsource (lib "eagle-import") (part "74LVC163"))
    )
    (comp (ref "U19")
      (value "74LVC163")
      (footprint "eagle-import:SO16D(SOT109)")
      (libsource (lib "eagle-import") (part "74LVC163"))
    )
    (comp (ref "U20")
      (value "74LVC163")
      (footprint "eagle-import:SO16D(SOT109)")
      (libsource (lib "eagle-import") (part "74LVC163"))
    )
    (comp (ref "U21")
      (value "74LVC163")
      (footprint "eagle-import:SO16D(SOT109)")
      (libsource (lib "eagle-import") (part "74LVC163"))
    )
    (comp (ref "U22")
      (value "74LVC595A")
      (footprint "eagle-import:SO16D(SOT109)")
      (libsource (lib "eagle-import") (part "74LVC595A"))
    )
    (comp (ref "U23")
      (value "74LVC595A")
      (footprint "eagle-import:SO16D(SOT109)")
      (libsource (lib "eagle-import") (part "74LVC595A"))
    )
    (comp (ref "U24")
      (value "74LVC595A")
      (footprint "eagle-import:SO16D(SOT109)")
      (libsource (lib "eagle-import") (part "74LVC595A"))
    )
    (comp (ref "U25")
      (value "74LVC595A")
      (footprint "eagle-import:SO16D(SOT109)")
      (libsource (lib "eagle-import") (part "74LVC595A"))
    )
    (comp (ref "U26")
      (value "ICS551")
      (footprint "eagle-import:SO08(SOT96)")
      (libsource (lib "eagle-import") (part "ICS551"))
    )
    (comp (ref "U27")
      (value "74LVC1G00")
      (footprint "eagle-import:SC70-5(SOT353)")
      (libsource (lib "eagle-import") (part "74LVC1G00"))
    )
    (comp (ref "U29")
      (value "74LVC109A")
      (footprint "eagle-import:SO16D(SOT109)")
      (libsource (lib "eagle-import") (part "74LVC109A"))
    )
    (comp (ref "U30")
      (value "74LVC109A")
      (footprint "eagle-import:SO16D(SOT109)")
      (libsource (lib "eagle-import") (part "74LVC109A"))
    )
    (comp (ref "U31")
      (value "74LVC1G00")
      (footprint "eagle-import:SC70-5(SOT353)")
      (libsource (lib "eagle-import") (part "74LVC1G00"))
    )
    (comp (ref "U32")
      (value "74AHC1G02DCK")
      (footprint "eagle-import:SC70-5(SOT353)")
      (libsource (lib "eagle-import") (part "74AHC1G02DCKSC70-5"))
    )
    (comp (ref "X1")
      (value "KC2520C-C2")
      (footprint "eagle-import:OSCXO2.5X2.0")
      (libsource (lib "eagle-import") (part "KC2520C-C2"))
    )
  )
  (nets
    (net (code "1") (name "+3V3") (class "Default")
      (node (ref "C10") (pin "2") (pinfunction "2_2") (pintype "passive"))
      (node (ref "C100") (pin "2") (pinfunction "2_2") (pintype "passive"))
      (node (ref "C101") (pin "2") (pinfunction "2_2") (pintype "passive"))
      (node (ref "C103") (pin "+") (pinfunction "+_+") (pintype "passive"))
      (node (ref "C104") (pin "2") (pinfunction "2_2") (pintype "passive"))
      (node (ref "C105") (pin "2") (pinfunction "2_2") (pintype "passive"))
      (node (ref "C11") (pin "2") (pinfunction "2_2") (pintype "passive"))
      (node (ref "C12") (pin "2") (pinfunction "2_2") (pintype "passive"))
      (node (ref "C13") (pin "2") (pinfunction "2_2") (pintype "passive"))
      (node (ref "C14") (pin "2") (pinfunction "2_2") (pintype "passive"))
      (node (ref "C15") (pin "2") (pinfunction "2_2") (pintype "passive"))
      (node (ref "C16") (pin "2") (pinfunction "2_2") (pintype "passive"))
      (node (ref "C17") (pin "2") (pinfunction "2_2") (pintype "passive"))
      (node (ref "C18") (pin "2") (pinfunction "2_2") (pintype "passive"))
      (node (ref "C19") (pin "2") (pinfunction "2_2") (pintype "passive"))
      (node (ref "C2") (pin "2") (pinfunction "2_2") (pintype "passive"))
      (node (ref "C20") (pin "2") (pinfunction "2_2") (pintype "passive"))
      (node (ref "C21") (pin "2") (pinfunction "2_2") (pintype "passive"))
      (node (ref "C22") (pin "2") (pinfunction "2_2") (pintype "passive"))
      (node (ref "C23") (pin "2") (pinfunction "2_2") (pintype "passive"))
      (node (ref "C24") (pin "2") (pinfunction "2_2") (pintype "passive"))
      (node (ref "C25") (pin "2") (pinfunction "2_2") (pintype "passive"))
      (node (ref "C26") (pin "2") (pinfunction "2_2") (pintype "passive"))
      (node (ref "C27") (pin "2") (pinfunction "2_2") (pintype "passive"))
      (node (ref "C28") (pin "2") (pinfunction "2_2") (pintype "passive"))
      (node (ref "C29") (pin "2") (pinfunction "2_2") (pintype "passive"))
      (node (ref "C3") (pin "2") (pinfunction "2_2") (pintype "passive"))
      (node (ref "C30") (pin "2") (pinfunction "2_2") (pintype "passive"))
      (node (ref "C31") (pin "2") (pinfunction "2_2") (pintype "passive"))
      (node (ref "C32") (pin "2") (pinfunction "2_2") (pintype "passive"))
      (node (ref "C33") (pin "2") (pinfunction "2_2") (pintype "passive"))
      (node (ref "C34") (pin "2") (pinfunction "2_2") (pintype "passive"))
      (node (ref "C35") (pin "2") (pinfunction "2_2") (pintype "passive"))
      (node (ref "C36") (pin "2") (pinfunction "2_2") (pintype "passive"))
      (node (ref "C37") (pin "2") (pinfunction "2_2") (pintype "passive"))
      (node (ref "C38") (pin "2") (pinfunction "2_2") (pintype "passive"))
      (node (ref "C39") (pin "2") (pinfunction "2_2") (pintype "passive"))
      (node (ref "C4") (pin "2") (pinfunction "2_2") (pintype "passive"))
      (node (ref "C40") (pin "2") (pinfunction "2_2") (pintype "passive"))
      (node (ref "C41") (pin "2") (pinfunction "2_2") (pintype "passive"))
      (node (ref "C42") (pin "2") (pinfunction "2_2") (pintype "passive"))
      (node (ref "C43") (pin "2") (pinfunction "2_2") (pintype "passive"))
      (node (ref "C44") (pin "2") (pinfunction "2_2") (pintype "passive"))
      (node (ref "C45") (pin "2") (pinfunction "2_2") (pintype "passive"))
      (node (ref "C46") (pin "2") (pinfunction "2_2") (pintype "passive"))
      (node (ref "C47") (pin "2") (pinfunction "2_2") (pintype "passive"))
      (node (ref "C48") (pin "2") (pinfunction "2_2") (pintype "passive"))
      (node (ref "C49") (pin "2") (pinfunction "2_2") (pintype "passive"))
      (node (ref "C5") (pin "2") (pinfunction "2_2") (pintype "passive"))
      (node (ref "C50") (pin "2") (pinfunction "2_2") (pintype "passive"))
      (node (ref "C51") (pin "2") (pinfunction "2_2") (pintype "passive"))
      (node (ref "C52") (pin "2") (pinfunction "2_2") (pintype "passive"))
      (node (ref "C53") (pin "2") (pinfunction "2_2") (pintype "passive"))
      (node (ref "C54") (pin "2") (pinfunction "2_2") (pintype "passive"))
      (node (ref "C55") (pin "2") (pinfunction "2_2") (pintype "passive"))
      (node (ref "C56") (pin "2") (pinfunction "2_2") (pintype "passive"))
      (node (ref "C57") (pin "2") (pinfunction "2_2") (pintype "passive"))
      (node (ref "C58") (pin "2") (pinfunction "2_2") (pintype "passive"))
      (node (ref "C59") (pin "2") (pinfunction "2_2") (pintype "passive"))
      (node (ref "C6") (pin "2") (pinfunction "2_2") (pintype "passive"))
      (node (ref "C60") (pin "2") (pinfunction "2_2") (pintype "passive"))
      (node (ref "C61") (pin "2") (pinfunction "2_2") (pintype "passive"))
      (node (ref "C62") (pin "2") (pinfunction "2_2") (pintype "passive"))
      (node (ref "C63") (pin "2") (pinfunction "2_2") (pintype "passive"))
      (node (ref "C64") (pin "2") (pinfunction "2_2") (pintype "passive"))
      (node (ref "C65") (pin "2") (pinfunction "2_2") (pintype "passive"))
      (node (ref "C66") (pin "2") (pinfunction "2_2") (pintype "passive"))
      (node (ref "C67") (pin "2") (pinfunction "2_2") (pintype "passive"))
      (node (ref "C68") (pin "2") (pinfunction "2_2") (pintype "passive"))
      (node (ref "C69") (pin "2") (pinfunction "2_2") (pintype "passive"))
      (node (ref "C7") (pin "2") (pinfunction "2_2") (pintype "passive"))
      (node (ref "C70") (pin "2") (pinfunction "2_2") (pintype "passive"))
      (node (ref "C71") (pin "2") (pinfunction "2_2") (pintype "passive"))
      (node (ref "C72") (pin "2") (pinfunction "2_2") (pintype "passive"))
      (node (ref "C73") (pin "2") (pinfunction "2_2") (pintype "passive"))
      (node (ref "C74") (pin "2") (pinfunction "2_2") (pintype "passive"))
      (node (ref "C75") (pin "2") (pinfunction "2_2") (pintype "passive"))
      (node (ref "C76") (pin "2") (pinfunction "2_2") (pintype "passive"))
      (node (ref "C77") (pin "2") (pinfunction "2_2") (pintype "passive"))
      (node (ref "C78") (pin "2") (pinfunction "2_2") (pintype "passive"))
      (node (ref "C79") (pin "2") (pinfunction "2_2") (pintype "passive"))
      (node (ref "C8") (pin "2") (pinfunction "2_2") (pintype "passive"))
      (node (ref "C80") (pin "2") (pinfunction "2_2") (pintype "passive"))
      (node (ref "C81") (pin "2") (pinfunction "2_2") (pintype "passive"))
      (node (ref "C9") (pin "2") (pinfunction "2_2") (pintype "passive"))
      (node (ref "C92") (pin "2") (pinfunction "2_2") (pintype "passive"))
      (node (ref "C93") (pin "2") (pinfunction "2_2") (pintype "passive"))
      (node (ref "C94") (pin "2") (pinfunction "2_2") (pintype "passive"))
      (node (ref "C95") (pin "2") (pinfunction "2_2") (pintype "passive"))
      (node (ref "C96") (pin "2") (pinfunction "2_2") (pintype "passive"))
      (node (ref "C97") (pin "2") (pinfunction "2_2") (pintype "passive"))
      (node (ref "C98") (pin "2") (pinfunction "2_2") (pintype "passive"))
      (node (ref "C99") (pin "2") (pinfunction "2_2") (pintype "passive"))
      (node (ref "D2") (pin "A") (pinfunction "A_A") (pintype "passive"))
      (node (ref "L1") (pin "2") (pinfunction "2_2") (pintype "passive"))
      (node (ref "LPC1769") (pin "28") (pinfunction "28_28") (pintype "passive"))
      (node (ref "SRAM1") (pin "11") (pinfunction "+3V3_11") (pintype "power_in"))
      (node (ref "SRAM1") (pin "33") (pinfunction "+3V3_33") (pintype "power_in"))
      (node (ref "SRAM2") (pin "11") (pinfunction "+3V3_11") (pintype "power_in"))
      (node (ref "SRAM2") (pin "33") (pinfunction "+3V3_33") (pintype "power_in"))
      (node (ref "U1") (pin "22") (pinfunction "+3V3_22") (pintype "power_in"))
      (node (ref "U1") (pin "35") (pinfunction "+3V3_35") (pintype "power_in"))
      (node (ref "U1") (pin "50") (pinfunction "+3V3_50") (pintype "power_in"))
      (node (ref "U1") (pin "7") (pinfunction "+3V3_7") (pintype "power_in"))
      (node (ref "U10") (pin "1") (pinfunction "DIR_1") (pintype "input"))
      (node (ref "U11") (pin "1") (pinfunction "DIR_1") (pintype "input"))
      (node (ref "U12") (pin "9") (pinfunction "PE_9") (pintype "input"))
      (node (ref "U14") (pin "9") (pinfunction "PE_9") (pintype "input"))
      (node (ref "U15") (pin "9") (pinfunction "PE_9") (pintype "input"))
      (node (ref "U16") (pin "9") (pinfunction "PE_9") (pintype "input"))
      (node (ref "U17") (pin "9") (pinfunction "PE_9") (pintype "input"))
      (node (ref "U18") (pin "9") (pinfunction "PE_9") (pintype "input"))
      (node (ref "U19") (pin "10") (pinfunction "CET_10") (pintype "input"))
      (node (ref "U19") (pin "7") (pinfunction "CEP_7") (pintype "input"))
      (node (ref "U19") (pin "9") (pinfunction "PE_9") (pintype "input"))
      (node (ref "U2") (pin "22") (pinfunction "+3V3_22") (pintype "power_in"))
      (node (ref "U2") (pin "35") (pinfunction "+3V3_35") (pintype "power_in"))
      (node (ref "U2") (pin "50") (pinfunction "+3V3_50") (pintype "power_in"))
      (node (ref "U2") (pin "7") (pinfunction "+3V3_7") (pintype "power_in"))
      (node (ref "U20") (pin "9") (pinfunction "PE_9") (pintype "input"))
      (node (ref "U21") (pin "9") (pinfunction "PE_9") (pintype "input"))
      (node (ref "U26") (pin "8") (pinfunction "OE_8") (pintype "input"))
      (node (ref "U28") (pin "1") (pinfunction "CLR_1") (pintype "input"))
      (node (ref "U28") (pin "10") (pinfunction "PRE_10") (pintype "input"))
      (node (ref "U28") (pin "11") (pinfunction "CLK_11") (pintype "input"))
      (node (ref "U28") (pin "12") (pinfunction "D_12") (pintype "input"))
      (node (ref "U28") (pin "13") (pinfunction "CLR_13") (pintype "input"))
      (node (ref "U28") (pin "4") (pinfunction "PRE_4") (pintype "input"))
      (node (ref "U29") (pin "1") (pinfunction "CLR_1") (pintype "input"))
      (node (ref "U29") (pin "11") (pinfunction "PRE_11") (pintype "input"))
      (node (ref "U29") (pin "15") (pinfunction "CLR_15") (pintype "input"))
      (node (ref "U29") (pin "5") (pinfunction "PRE_5") (pintype "input"))
      (node (ref "U3") (pin "22") (pinfunction "+3V3_22") (pintype "power_in"))
      (node (ref "U3") (pin "35") (pinfunction "+3V3_35") (pintype "power_in"))
      (node (ref "U3") (pin "50") (pinfunction "+3V3_50") (pintype "power_in"))
      (node (ref "U3") (pin "7") (pinfunction "+3V3_7") (pintype "power_in"))
      (node (ref "U30") (pin "1") (pinfunction "CLR_1") (pintype "input"))
      (node (ref "U30") (pin "11") (pinfunction "PRE_11") (pintype "input"))
      (node (ref "U30") (pin "15") (pinfunction "CLR_15") (pintype "input"))
      (node (ref "U30") (pin "5") (pinfunction "PRE_5") (pintype "input"))
      (node (ref "U4") (pin "22") (pinfunction "+3V3_22") (pintype "power_in"))
      (node (ref "U4") (pin "35") (pinfunction "+3V3_35") (pintype "power_in"))
      (node (ref "U4") (pin "50") (pinfunction "+3V3_50") (pintype "power_in"))
      (node (ref "U4") (pin "7") (pinfunction "+3V3_7") (pintype "power_in"))
      (node (ref "U5") (pin "10") (pinfunction "CET_10") (pintype "input"))
      (node (ref "U5") (pin "7") (pinfunction "CEP_7") (pintype "input"))
      (node (ref "U5") (pin "9") (pinfunction "PE_9") (pintype "input"))
      (node (ref "U6") (pin "10") (pinfunction "CET_10") (pintype "input"))
      (node (ref "U6") (pin "7") (pinfunction "CEP_7") (pintype "input"))
      (node (ref "U6") (pin "9") (pinfunction "PE_9") (pintype "input"))
      (node (ref "U7") (pin "10") (pinfunction "PRE_10") (pintype "input"))
      (node (ref "U7") (pin "11") (pinfunction "J_11") (pintype "input"))
      (node (ref "U7") (pin "12") (pinfunction "K_12") (pintype "input"))
      (node (ref "U7") (pin "13") (pinfunction "CLK_13") (pintype "input"))
      (node (ref "U7") (pin "14") (pinfunction "CLR_14") (pintype "input"))
      (node (ref "U7") (pin "15") (pinfunction "CLR_15") (pintype "input"))
      (node (ref "U7") (pin "2") (pinfunction "K_2") (pintype "input"))
      (node (ref "U8") (pin "1") (pinfunction "DIR_1") (pintype "input"))
      (node (ref "U9") (pin "1") (pinfunction "DIR_1") (pintype "input"))
      (node (ref "X1") (pin "4") (pinfunction "+3V3_4") (pintype "power_in"))
      (node (ref "X2") (pin "2") (pinfunction "K_2") (pintype "passive"))
    )
    (net (code "2") (name "+3VA") (class "Default")
      (node (ref "ADV7125") (pin "12") (pinfunction "~{SYNC}_12") (pintype "input"))
      (node (ref "ADV7125") (pin "13") (pinfunction "VAA_13") (pintype "power_in"))
      (node (ref "ADV7125") (pin "29") (pinfunction "VAA_29") (pintype "power_in"))
      (node (ref "ADV7125") (pin "30") (pinfunction "VAA_30") (pintype "power_in"))
      (node (ref "ADV7125") (pin "38") (pinfunction "~{PSAVE}_38") (pintype "input"))
      (node (ref "C1") (pin "2") (pinfunction "2_2") (pintype "passive"))
      (node (ref "C82") (pin "2") (pinfunction "2_2") (pintype "passive"))
      (node (ref "C83") (pin "2") (pinfunction "2_2") (pintype "passive"))
      (node (ref "C84") (pin "2") (pinfunction "2_2") (pintype "passive"))
      (node (ref "C85") (pin "2") (pinfunction "2_2") (pintype "passive"))
      (node (ref "C86") (pin "2") (pinfunction "2_2") (pintype "passive"))
      (node (ref "C87") (pin "2") (pinfunction "2_2") (pintype "passive"))
      (node (ref "L1") (pin "1") (pinfunction "1_1") (pintype "passive"))
      (node (ref "R8") (pin "2") (pinfunction "2_2") (pintype "passive"))
    )
    (net (code "12") (name "40MHZ_CLK") (class "Default")
      (node (ref "U26") (pin "1") (pinfunction "ICLK_1") (pintype "input"))
      (node (ref "X1") (pin "3") (pinfunction "OUT_3") (pintype "output"))
    )
    (net (code "13") (name "AGND") (class "Default")
      (node (ref "ADV7125") (pin "1") (pinfunction "GND_1") (pintype "passive"))
      (node (ref "ADV7125") (pin "14") (pinfunction "GND_14") (pintype "passive"))
      (node (ref "ADV7125") (pin "15") (pinfunction "GND_15") (pintype "passive"))
      (node (ref "ADV7125") (pin "2") (pinfunction "GND_2") (pintype "passive"))
      (node (ref "ADV7125") (pin "25") (pinfunction "GND_25") (pintype "passive"))
      (node (ref "ADV7125") (pin "26") (pinfunction "GND_26") (pintype "passive"))
      (node (ref "ADV7125") (pin "27") (pinfunction "~{IOB}_27") (pintype "output"))
      (node (ref "ADV7125") (pin "31") (pinfunction "~{IOG}_31") (pintype "output"))
      (node (ref "ADV7125") (pin "33") (pinfunction "~{IOR}_33") (pintype "output"))
      (node (ref "ADV7125") (pin "39") (pinfunction "GND_39") (pintype "passive"))
      (node (ref "ADV7125") (pin "40") (pinfunction "GND_40") (pintype "passive"))
      (node (ref "C82") (pin "1") (pinfunction "1_1") (pintype "passive"))
      (node (ref "C83") (pin "1") (pinfunction "1_1") (pintype "passive"))
      (node (ref "C84") (pin "1") (pinfunction "1_1") (pintype "passive"))
      (node (ref "C85") (pin "1") (pinfunction "1_1") (pintype "passive"))
      (node (ref "C86") (pin "1") (pinfunction "1_1") (pintype "passive"))
      (node (ref "C87") (pin "1") (pinfunction "1_1") (pintype "passive"))
      (node (ref "C91") (pin "1") (pinfunction "1_1") (pintype "passive"))
      (node (ref "D1") (pin "2") (pinfunction "V-_2") (pintype "passive"))
      (node (ref "J1") (pin "5") (pinfunction "GND_5") (pintype "passive"))
      (node (ref "J1") (pin "6") (pinfunction "RGND_6") (pintype "passive"))
      (node (ref "J1") (pin "7") (pinfunction "GGND_7") (pintype "passive"))
      (node (ref "J1") (pin "8") (pinfunction "BGND_8") (pintype "passive"))
      (node (ref "L2") (pin "2") (pinfunction "2_2") (pintype "passive"))
      (node (ref "R1") (pin "1") (pinfunction "1_1") (pintype "passive"))
      (node (ref "R2") (pin "1") (pinfunction "1_1") (pintype "passive"))
      (node (ref "R3") (pin "1") (pinfunction "1_1") (pintype "passive"))
      (node (ref "R4") (pin "1") (pinfunction "1_1") (pintype "passive"))
    )
    (net (code "14") (name "A_IN0") (class "Default")
      (node (ref "U1") (pin "30") (pinfunction "2A10_30") (pintype "input"))
      (node (ref "U23") (pin "15") (pinfunction "Q0_15") (pintype "output"))
      (node (ref "U3") (pin "55") (pinfunction "1A1_55") (pintype "input"))
    )
    (net (code "15") (name "A_IN1") (class "Default")
      (node (ref "U1") (pin "31") (pinfunction "2A9_31") (pintype "input"))
      (node (ref "U23") (pin "1") (pinfunction "Q1_1") (pintype "output"))
      (node (ref "U3") (pin "54") (pinfunction "1A2_54") (pintype "input"))
    )
    (net (code "16") (name "A_IN2") (class "Default")
      (node (ref "U1") (pin "33") (pinfunction "2A8_33") (pintype "input"))
      (node (ref "U23") (pin "2") (pinfunction "Q2_2") (pintype "output"))
      (node (ref "U3") (pin "52") (pinfunction "1A3_52") (pintype "input"))
    )
    (net (code "17") (name "A_IN3") (class "Default")
      (node (ref "U1") (pin "34") (pinfunction "2A7_34") (pintype "input"))
      (node (ref "U23") (pin "3") (pinfunction "Q3_3") (pintype "output"))
      (node (ref "U3") (pin "51") (pinfunction "1A4_51") (pintype "input"))
    )
    (net (code "18") (name "A_IN4") (class "Default")
      (node (ref "U1") (pin "36") (pinfunction "2A6_36") (pintype "input"))
      (node (ref "U23") (pin "4") (pinfunction "Q4_4") (pintype "output"))
      (node (ref "U3") (pin "49") (pinfunction "1A5_49") (pintype "input"))
    )
    (net (code "19") (name "A_IN5") (class "Default")
      (node (ref "U1") (pin "37") (pinfunction "2A5_37") (pintype "input"))
      (node (ref "U23") (pin "5") (pinfunction "Q5_5") (pintype "output"))
      (node (ref "U3") (pin "48") (pinfunction "1A6_48") (pintype "input"))
    )
    (net (code "20") (name "A_IN6") (class "Default")
      (node (ref "U1") (pin "38") (pinfunction "2A4_38") (pintype "input"))
      (node (ref "U23") (pin "6") (pinfunction "Q6_6") (pintype "output"))
      (node (ref "U3") (pin "47") (pinfunction "1A7_47") (pintype "input"))
    )
    (net (code "21") (name "A_IN7") (class "Default")
      (node (ref "U1") (pin "40") (pinfunction "2A3_40") (pintype "input"))
      (node (ref "U23") (pin "7") (pinfunction "Q7_7") (pintype "output"))
      (node (ref "U3") (pin "45") (pinfunction "1A8_45") (pintype "input"))
    )
    (net (code "22") (name "A_IN8") (class "Default")
      (node (ref "U1") (pin "41") (pinfunction "2A2_41") (pintype "input"))
      (node (ref "U24") (pin "15") (pinfunction "Q0_15") (pintype "output"))
      (node (ref "U3") (pin "44") (pinfunction "1A9_44") (pintype "input"))
    )
    (net (code "23") (name "A_IN9") (class "Default")
      (node (ref "U1") (pin "42") (pinfunction "2A1_42") (pintype "input"))
      (node (ref "U24") (pin "1") (pinfunction "Q1_1") (pintype "output"))
      (node (ref "U3") (pin "43") (pinfunction "1A10_43") (pintype "input"))
    )
    (net (code "24") (name "A_IN10") (class "Default")
      (node (ref "U1") (pin "43") (pinfunction "1A10_43") (pintype "input"))
      (node (ref "U24") (pin "2") (pinfunction "Q2_2") (pintype "output"))
      (node (ref "U3") (pin "42") (pinfunction "2A1_42") (pintype "input"))
    )
    (net (code "25") (name "A_IN11") (class "Default")
      (node (ref "U1") (pin "44") (pinfunction "1A9_44") (pintype "input"))
      (node (ref "U24") (pin "3") (pinfunction "Q3_3") (pintype "output"))
      (node (ref "U3") (pin "41") (pinfunction "2A2_41") (pintype "input"))
    )
    (net (code "26") (name "A_IN12") (class "Default")
      (node (ref "U1") (pin "45") (pinfunction "1A8_45") (pintype "input"))
      (node (ref "U24") (pin "4") (pinfunction "Q4_4") (pintype "output"))
      (node (ref "U3") (pin "40") (pinfunction "2A3_40") (pintype "input"))
    )
    (net (code "27") (name "A_IN13") (class "Default")
      (node (ref "U1") (pin "47") (pinfunction "1A7_47") (pintype "input"))
      (node (ref "U24") (pin "5") (pinfunction "Q5_5") (pintype "output"))
      (node (ref "U3") (pin "38") (pinfunction "2A4_38") (pintype "input"))
    )
    (net (code "28") (name "A_IN14") (class "Default")
      (node (ref "U1") (pin "48") (pinfunction "1A6_48") (pintype "input"))
      (node (ref "U24") (pin "6") (pinfunction "Q6_6") (pintype "output"))
      (node (ref "U3") (pin "37") (pinfunction "2A5_37") (pintype "input"))
    )
    (net (code "29") (name "A_IN15") (class "Default")
      (node (ref "U1") (pin "49") (pinfunction "1A5_49") (pintype "input"))
      (node (ref "U24") (pin "7") (pinfunction "Q7_7") (pintype "output"))
      (node (ref "U3") (pin "36") (pinfunction "2A6_36") (pintype "input"))
    )
    (net (code "30") (name "A_IN16") (class "Default")
      (node (ref "U1") (pin "51") (pinfunction "1A4_51") (pintype "input"))
      (node (ref "U25") (pin "15") (pinfunction "Q0_15") (pintype "output"))
      (node (ref "U3") (pin "34") (pinfunction "2A7_34") (pintype "input"))
    )
    (net (code "31") (name "A_IN17") (class "Default")
      (node (ref "U1") (pin "52") (pinfunction "1A3_52") (pintype "input"))
      (node (ref "U25") (pin "1") (pinfunction "Q1_1") (pintype "output"))
      (node (ref "U3") (pin "33") (pinfunction "2A8_33") (pintype "input"))
    )
    (net (code "32") (name "A_IN18") (class "Default")
      (node (ref "U1") (pin "54") (pinfunction "1A2_54") (pintype "input"))
      (node (ref "U25") (pin "2") (pinfunction "Q2_2") (pintype "output"))
      (node (ref "U3") (pin "31") (pinfunction "2A9_31") (pintype "input"))
    )
    (net (code "33") (name "A_IN19") (class "Default")
      (node (ref "U1") (pin "55") (pinfunction "1A1_55") (pintype "input"))
      (node (ref "U25") (pin "3") (pinfunction "Q3_3") (pintype "output"))
      (node (ref "U3") (pin "30") (pinfunction "2A10_30") (pintype "input"))
    )
    (net (code "34") (name "B0") (class "Default")
      (node (ref "ADV7125") (pin "16") (pinfunction "B0_16") (pintype "input"))
      (node (ref "ADV7125") (pin "18") (pinfunction "B2_18") (pintype "input"))
      (node (ref "ADV7125") (pin "20") (pinfunction "B4_20") (pintype "input"))
      (node (ref "ADV7125") (pin "22") (pinfunction "B6_22") (pintype "input"))
      (node (ref "U10") (pin "11") (pinfunction "B8_11") (pintype "output"))
      (node (ref "U11") (pin "18") (pinfunction "B1_18") (pintype "output"))
    )
    (net (code "35") (name "B1") (class "Default")
      (node (ref "ADV7125") (pin "17") (pinfunction "B1_17") (pintype "input"))
      (node (ref "ADV7125") (pin "19") (pinfunction "B3_19") (pintype "input"))
      (node (ref "ADV7125") (pin "21") (pinfunction "B5_21") (pintype "input"))
      (node (ref "ADV7125") (pin "23") (pinfunction "B7_23") (pintype "input"))
      (node (ref "U10") (pin "12") (pinfunction "B7_12") (pintype "output"))
      (node (ref "U11") (pin "17") (pinfunction "B2_17") (pintype "output"))
    )
    (net (code "36") (name "CCLK0") (class "Default")
      (node (ref "R9") (pin "2") (pinfunction "2_2") (pintype "passive"))
      (node (ref "U17") (pin "2") (pinfunction "CLK_2") (pintype "input"))
      (node (ref "U18") (pin "2") (pinfunction "CLK_2") (pintype "input"))
      (node (ref "U26") (pin "2") (pinfunction "Q1_2") (pintype "output"))
      (node (ref "U6") (pin "2") (pinfunction "CLK_2") (pintype "input"))
    )
    (net (code "37") (name "CCLK1") (class "Default")
      (node (ref "ADV7125") (pin "24") (pinfunction "CLOCK_24") (pintype "input"))
      (node (ref "R11") (pin "2") (pinfunction "2_2") (pintype "passive"))
      (node (ref "U26") (pin "3") (pinfunction "Q2_3") (pintype "output"))
    )
    (net (code "38") (name "CCLK2") (class "Default")
      (node (ref "R5") (pin "2") (pinfunction "2_2") (pintype "passive"))
      (node (ref "U12") (pin "2") (pinfunction "CLK_2") (pintype "input"))
      (node (ref "U14") (pin "2") (pinfunction "CLK_2") (pintype "input"))
      (node (ref "U15") (pin "2") (pinfunction "CLK_2") (pintype "input"))
      (node (ref "U16") (pin "2") (pinfunction "CLK_2") (pintype "input"))
      (node (ref "U26") (pin "4") (pinfunction "Q3_4") (pintype "output"))
      (node (ref "U5") (pin "2") (pinfunction "CLK_2") (pintype "input"))
    )
    (net (code "39") (name "CCLK3") (class "Default")
      (node (ref "U26") (pin "5") (pinfunction "Q4_5") (pintype "output"))
      (node (ref "U29") (pin "12") (pinfunction "CLK_12") (pintype "input"))
      (node (ref "U29") (pin "4") (pinfunction "CLK_4") (pintype "input"))
      (node (ref "U30") (pin "12") (pinfunction "CLK_12") (pintype "input"))
      (node (ref "U30") (pin "4") (pinfunction "CLK_4") (pintype "input"))
    )
    (net (code "40") (name "CS") (class "Default")
      (node (ref "LPC1769") (pin "14") (pinfunction "14_14") (pintype "passive"))
      (node (ref "U28") (pin "2") (pinfunction "D_2") (pintype "input"))
    )
    (net (code "41") (name "D_IN0") (class "Default")
      (node (ref "U22") (pin "15") (pinfunction "Q0_15") (pintype "output"))
      (node (ref "U8") (pin "9") (pinfunction "A8_9") (pintype "input"))
      (node (ref "U9") (pin "2") (pinfunction "A1_2") (pintype "input"))
    )
    (net (code "42") (name "D_IN1") (class "Default")
      (node (ref "U22") (pin "1") (pinfunction "Q1_1") (pintype "output"))
      (node (ref "U8") (pin "8") (pinfunction "A7_8") (pintype "input"))
      (node (ref "U9") (pin "3") (pinfunction "A2_3") (pintype "input"))
    )
    (net (code "43") (name "D_IN2") (class "Default")
      (node (ref "U22") (pin "2") (pinfunction "Q2_2") (pintype "output"))
      (node (ref "U8") (pin "7") (pinfunction "A6_7") (pintype "input"))
      (node (ref "U9") (pin "4") (pinfunction "A3_4") (pintype "input"))
    )
    (net (code "44") (name "D_IN3") (class "Default")
      (node (ref "U22") (pin "3") (pinfunction "Q3_3") (pintype "output"))
      (node (ref "U8") (pin "6") (pinfunction "A5_6") (pintype "input"))
      (node (ref "U9") (pin "5") (pinfunction "A4_5") (pintype "input"))
    )
    (net (code "45") (name "D_IN4") (class "Default")
      (node (ref "U22") (pin "4") (pinfunction "Q4_4") (pintype "output"))
      (node (ref "U8") (pin "5") (pinfunction "A4_5") (pintype "input"))
      (node (ref "U9") (pin "6") (pinfunction "A5_6") (pintype "input"))
    )
    (net (code "46") (name "D_IN5") (class "Default")
      (node (ref "U22") (pin "5") (pinfunction "Q5_5") (pintype "output"))
      (node (ref "U8") (pin "4") (pinfunction "A3_4") (pintype "input"))
      (node (ref "U9") (pin "7") (pinfunction "A6_7") (pintype "input"))
    )
    (net (code "47") (name "D_IN6") (class "Default")
      (node (ref "U22") (pin "6") (pinfunction "Q6_6") (pintype "output"))
      (node (ref "U8") (pin "3") (pinfunction "A2_3") (pintype "input"))
      (node (ref "U9") (pin "8") (pinfunction "A7_8") (pintype "input"))
    )
    (net (code "48") (name "D_IN7") (class "Default")
      (node (ref "U22") (pin "7") (pinfunction "Q7_7") (pintype "output"))
      (node (ref "U8") (pin "2") (pinfunction "A1_2") (pintype "input"))
      (node (ref "U9") (pin "9") (pinfunction "A8_9") (pintype "input"))
    )
    (net (code "49") (name "D_READY") (class "Default")
      (node (ref "U22") (pin "12") (pinfunction "STCP_12") (pintype "input"))
      (node (ref "U23") (pin "12") (pinfunction "STCP_12") (pintype "input"))
      (node (ref "U24") (pin "12") (pinfunction "STCP_12") (pintype "input"))
      (node (ref "U25") (pin "12") (pinfunction "STCP_12") (pintype "input"))
      (node (ref "U25") (pin "9") (pinfunction "Q7S_9") (pintype "output"))
      (node (ref "U32") (pin "2") (pinfunction "B_2") (pintype "input"))
    )
    (net (code "50") (name "G0") (class "Default")
      (node (ref "ADV7125") (pin "5") (pinfunction "G2_5") (pintype "input"))
      (node (ref "ADV7125") (pin "8") (pinfunction "G5_8") (pintype "input"))
      (node (ref "U10") (pin "13") (pinfunction "B6_13") (pintype "output"))
      (node (ref "U11") (pin "16") (pinfunction "B3_16") (pintype "output"))
    )
    (net (code "51") (name "G1") (class "Default")
      (node (ref "ADV7125") (pin "3") (pinfunction "G0_3") (pintype "input"))
      (node (ref "ADV7125") (pin "6") (pinfunction "G3_6") (pintype "input"))
      (node (ref "ADV7125") (pin "9") (pinfunction "G6_9") (pintype "input"))
      (node (ref "U10") (pin "14") (pinfunction "B5_14") (pintype "output"))
      (node (ref "U11") (pin "15") (pinfunction "B4_15") (pintype "output"))
    )
    (net (code "52") (name "G2") (class "Default")
      (node (ref "ADV7125") (pin "10") (pinfunction "G7_10") (pintype "input"))
      (node (ref "ADV7125") (pin "4") (pinfunction "G1_4") (pintype "input"))
      (node (ref "ADV7125") (pin "7") (pinfunction "G4_7") (pintype "input"))
      (node (ref "U10") (pin "15") (pinfunction "B4_15") (pintype "output"))
      (node (ref "U11") (pin "14") (pinfunction "B5_14") (pintype "output"))
    )
    (net (code "53") (name "GND") (class "Default")
      (node (ref "C10") (pin "1") (pinfunction "1_1") (pintype "passive"))
      (node (ref "C100") (pin "1") (pinfunction "1_1") (pintype "passive"))
      (node (ref "C101") (pin "1") (pinfunction "1_1") (pintype "passive"))
      (node (ref "C102") (pin "1") (pinfunction "1_1") (pintype "passive"))
      (node (ref "C103") (pin "-") (pinfunction "-_-") (pintype "passive"))
      (node (ref "C104") (pin "1") (pinfunction "1_1") (pintype "passive"))
      (node (ref "C105") (pin "1") (pinfunction "1_1") (pintype "passive"))
      (node (ref "C11") (pin "1") (pinfunction "1_1") (pintype "passive"))
      (node (ref "C12") (pin "1") (pinfunction "1_1") (pintype "passive"))
      (node (ref "C13") (pin "1") (pinfunction "1_1") (pintype "passive"))
      (node (ref "C14") (pin "1") (pinfunction "1_1") (pintype "passive"))
      (node (ref "C15") (pin "1") (pinfunction "1_1") (pintype "passive"))
      (node (ref "C16") (pin "1") (pinfunction "1_1") (pintype "passive"))
      (node (ref "C17") (pin "1") (pinfunction "1_1") (pintype "passive"))
      (node (ref "C18") (pin "1") (pinfunction "1_1") (pintype "passive"))
      (node (ref "C19") (pin "1") (pinfunction "1_1") (pintype "passive"))
      (node (ref "C2") (pin "1") (pinfunction "1_1") (pintype "passive"))
      (node (ref "C20") (pin "1") (pinfunction "1_1") (pintype "passive"))
      (node (ref "C21") (pin "1") (pinfunction "1_1") (pintype "passive"))
      (node (ref "C22") (pin "1") (pinfunction "1_1") (pintype "passive"))
      (node (ref "C23") (pin "1") (pinfunction "1_1") (pintype "passive"))
      (node (ref "C24") (pin "1") (pinfunction "1_1") (pintype "passive"))
      (node (ref "C25") (pin "1") (pinfunction "1_1") (pintype "passive"))
      (node (ref "C26") (pin "1") (pinfunction "1_1") (pintype "passive"))
      (node (ref "C27") (pin "1") (pinfunction "1_1") (pintype "passive"))
      (node (ref "C28") (pin "1") (pinfunction "1_1") (pintype "passive"))
      (node (ref "C29") (pin "1") (pinfunction "1_1") (pintype "passive"))
      (node (ref "C3") (pin "1") (pinfunction "1_1") (pintype "passive"))
      (node (ref "C30") (pin "1") (pinfunction "1_1") (pintype "passive"))
      (node (ref "C31") (pin "1") (pinfunction "1_1") (pintype "passive"))
      (node (ref "C32") (pin "1") (pinfunction "1_1") (pintype "passive"))
      (node (ref "C33") (pin "1") (pinfunction "1_1") (pintype "passive"))
      (node (ref "C34") (pin "1") (pinfunction "1_1") (pintype "passive"))
      (node (ref "C35") (pin "1") (pinfunction "1_1") (pintype "passive"))
      (node (ref "C36") (pin "1") (pinfunction "1_1") (pintype "passive"))
      (node (ref "C37") (pin "1") (pinfunction "1_1") (pintype "passive"))
      (node (ref "C38") (pin "1") (pinfunction "1_1") (pintype "passive"))
      (node (ref "C39") (pin "1") (pinfunction "1_1") (pintype "passive"))
      (node (ref "C4") (pin "1") (pinfunction "1_1") (pintype "passive"))
      (node (ref "C40") (pin "1") (pinfunction "1_1") (pintype "passive"))
      (node (ref "C41") (pin "1") (pinfunction "1_1") (pintype "passive"))
      (node (ref "C42") (pin "1") (pinfunction "1_1") (pintype "passive"))
      (node (ref "C43") (pin "1") (pinfunction "1_1") (pintype "passive"))
      (node (ref "C44") (pin "1") (pinfunction "1_1") (pintype "passive"))
      (node (ref "C45") (pin "1") (pinfunction "1_1") (pintype "passive"))
      (node (ref "C46") (pin "1") (pinfunction "1_1") (pintype "passive"))
      (node (ref "C47") (pin "1") (pinfunction "1_1") (pintype "passive"))
      (node (ref "C48") (pin "1") (pinfunction "1_1") (pintype "passive"))
      (node (ref "C49") (pin "1") (pinfunction "1_1") (pintype "passive"))
      (node (ref "C5") (pin "1") (pinfunction "1_1") (pintype "passive"))
      (node (ref "C50") (pin "1") (pinfunction "1_1") (pintype "passive"))
      (node (ref "C51") (pin "1") (pinfunction "1_1") (pintype "passive"))
      (node (ref "C52") (pin "1") (pinfunction "1_1") (pintype "passive"))
      (node (ref "C53") (pin "1") (pinfunction "1_1") (pintype "passive"))
      (node (ref "C54") (pin "1") (pinfunction "1_1") (pintype "passive"))
      (node (ref "C55") (pin "1") (pinfunction "1_1") (pintype "passive"))
      (node (ref "C56") (pin "1") (pinfunction "1_1") (pintype "passive"))
      (node (ref "C57") (pin "1") (pinfunction "1_1") (pintype "passive"))
      (node (ref "C58") (pin "1") (pinfunction "1_1") (pintype "passive"))
      (node (ref "C59") (pin "1") (pinfunction "1_1") (pintype "passive"))
      (node (ref "C6") (pin "1") (pinfunction "1_1") (pintype "passive"))
      (node (ref "C60") (pin "1") (pinfunction "1_1") (pintype "passive"))
      (node (ref "C61") (pin "1") (pinfunction "1_1") (pintype "passive"))
      (node (ref "C62") (pin "1") (pinfunction "1_1") (pintype "passive"))
      (node (ref "C63") (pin "1") (pinfunction "1_1") (pintype "passive"))
      (node (ref "C64") (pin "1") (pinfunction "1_1") (pintype "passive"))
      (node (ref "C65") (pin "1") (pinfunction "1_1") (pintype "passive"))
      (node (ref "C66") (pin "1") (pinfunction "1_1") (pintype "passive"))
      (node (ref "C67") (pin "1") (pinfunction "1_1") (pintype "passive"))
      (node (ref "C68") (pin "1") (pinfunction "1_1") (pintype "passive"))
      (node (ref "C69") (pin "1") (pinfunction "1_1") (pintype "passive"))
      (node (ref "C7") (pin "1") (pinfunction "1_1") (pintype "passive"))
      (node (ref "C70") (pin "1") (pinfunction "1_1") (pintype "passive"))
      (node (ref "C71") (pin "1") (pinfunction "1_1") (pintype "passive"))
      (node (ref "C72") (pin "1") (pinfunction "1_1") (pintype "passive"))
      (node (ref "C73") (pin "1") (pinfunction "1_1") (pintype "passive"))
      (node (ref "C74") (pin "1") (pinfunction "1_1") (pintype "passive"))
      (node (ref "C75") (pin "1") (pinfunction "1_1") (pintype "passive"))
      (node (ref "C76") (pin "1") (pinfunction "1_1") (pintype "passive"))
      (node (ref "C77") (pin "1") (pinfunction "1_1") (pintype "passive"))
      (node (ref "C78") (pin "1") (pinfunction "1_1") (pintype "passive"))
      (node (ref "C79") (pin "1") (pinfunction "1_1") (pintype "passive"))
      (node (ref "C8") (pin "1") (pinfunction "1_1") (pintype "passive"))
      (node (ref "C80") (pin "1") (pinfunction "1_1") (pintype "passive"))
      (node (ref "C81") (pin "1") (pinfunction "1_1") (pintype "passive"))
      (node (ref "C88") (pin "1") (pinfunction "1_1") (pintype "passive"))
      (node (ref "C89") (pin "1") (pinfunction "1_1") (pintype "passive"))
      (node (ref "C9") (pin "1") (pinfunction "1_1") (pintype "passive"))
      (node (ref "C90") (pin "1") (pinfunction "1_1") (pintype "passive"))
      (node (ref "C92") (pin "1") (pinfunction "1_1") (pintype "passive"))
      (node (ref "C93") (pin "1") (pinfunction "1_1") (pintype "passive"))
      (node (ref "C94") (pin "1") (pinfunction "1_1") (pintype "passive"))
      (node (ref "C95") (pin "1") (pinfunction "1_1") (pintype "passive"))
      (node (ref "C96") (pin "1") (pinfunction "1_1") (pintype "passive"))
      (node (ref "C97") (pin "1") (pinfunction "1_1") (pintype "passive"))
      (node (ref "C98") (pin "1") (pinfunction "1_1") (pintype "passive"))
      (node (ref "C99") (pin "1") (pinfunction "1_1") (pintype "passive"))
      (node (ref "IC6") (pin "11") (pinfunction "I10_11") (pintype "input"))
      (node (ref "IC6") (pin "13") (pinfunction "I11_13") (pintype "input"))
      (node (ref "J1") (pin "10") (pinfunction "SGND_10") (pintype "passive"))
      (node (ref "LPC1769") (pin "54") (pinfunction "54_54") (pintype "passive"))
      (node (ref "R12") (pin "2") (pinfunction "2_2") (pintype "passive"))
      (node (ref "SRAM1") (pin "12") (pinfunction "GND_12") (pintype "power_in"))
      (node (ref "SRAM1") (pin "34") (pinfunction "GND_34") (pintype "power_in"))
      (node (ref "SRAM1") (pin "8") (pinfunction "CE_8") (pintype "input"))
      (node (ref "SRAM2") (pin "12") (pinfunction "GND_12") (pintype "power_in"))
      (node (ref "SRAM2") (pin "34") (pinfunction "GND_34") (pintype "power_in"))
      (node (ref "SRAM2") (pin "8") (pinfunction "CE_8") (pintype "input"))
      (node (ref "U1") (pin "11") (pinfunction "GND_11") (pintype "power_in"))
      (node (ref "U1") (pin "18") (pinfunction "GND_18") (pintype "power_in"))
      (node (ref "U1") (pin "25") (pinfunction "GND_25") (pintype "power_in"))
      (node (ref "U1") (pin "32") (pinfunction "GND_32") (pintype "power_in"))
      (node (ref "U1") (pin "39") (pinfunction "GND_39") (pintype "power_in"))
      (node (ref "U1") (pin "4") (pinfunction "GND_4") (pintype "power_in"))
      (node (ref "U1") (pin "46") (pinfunction "GND_46") (pintype "power_in"))
      (node (ref "U1") (pin "53") (pinfunction "GND_53") (pintype "power_in"))
      (node (ref "U12") (pin "3") (pinfunction "D0_3") (pintype "input"))
      (node (ref "U12") (pin "4") (pinfunction "D1_4") (pintype "input"))
      (node (ref "U12") (pin "5") (pinfunction "D2_5") (pintype "input"))
      (node (ref "U12") (pin "6") (pinfunction "D3_6") (pintype "input"))
      (node (ref "U14") (pin "3") (pinfunction "D0_3") (pintype "input"))
      (node (ref "U14") (pin "4") (pinfunction "D1_4") (pintype "input"))
      (node (ref "U14") (pin "5") (pinfunction "D2_5") (pintype "input"))
      (node (ref "U14") (pin "6") (pinfunction "D3_6") (pintype "input"))
      (node (ref "U15") (pin "3") (pinfunction "D0_3") (pintype "input"))
      (node (ref "U15") (pin "4") (pinfunction "D1_4") (pintype "input"))
      (node (ref "U15") (pin "5") (pinfunction "D2_5") (pintype "input"))
      (node (ref "U15") (pin "6") (pinfunction "D3_6") (pintype "input"))
      (node (ref "U16") (pin "3") (pinfunction "D0_3") (pintype "input"))
      (node (ref "U16") (pin "4") (pinfunction "D1_4") (pintype "input"))
      (node (ref "U16") (pin "5") (pinfunction "D2_5") (pintype "input"))
      (node (ref "U16") (pin "6") (pinfunction "D3_6") (pintype "input"))
      (node (ref "U17") (pin "3") (pinfunction "D0_3") (pintype "input"))
      (node (ref "U17") (pin "4") (pinfunction "D1_4") (pintype "input"))
      (node (ref "U17") (pin "5") (pinfunction "D2_5") (pintype "input"))
      (node (ref "U17") (pin "6") (pinfunction "D3_6") (pintype "input"))
      (node (ref "U18") (pin "3") (pinfunction "D0_3") (pintype "input"))
      (node (ref "U18") (pin "4") (pinfunction "D1_4") (pintype "input"))
      (node (ref "U18") (pin "5") (pinfunction "D2_5") (pintype "input"))
      (node (ref "U18") (pin "6") (pinfunction "D3_6") (pintype "input"))
      (node (ref "U19") (pin "3") (pinfunction "D0_3") (pintype "input"))
      (node (ref "U19") (pin "4") (pinfunction "D1_4") (pintype "input"))
      (node (ref "U19") (pin "5") (pinfunction "D2_5") (pintype "input"))
      (node (ref "U19") (pin "6") (pinfunction "D3_6") (pintype "input"))
      (node (ref "U2") (pin "11") (pinfunction "GND_11") (pintype "power_in"))
      (node (ref "U2") (pin "18") (pinfunction "GND_18") (pintype "power_in"))
      (node (ref "U2") (pin "25") (pinfunction "GND_25") (pintype "power_in"))
      (node (ref "U2") (pin "32") (pinfunction "GND_32") (pintype "power_in"))
      (node (ref "U2") (pin "39") (pinfunction "GND_39") (pintype "power_in"))
      (node (ref "U2") (pin "4") (pinfunction "GND_4") (pintype "power_in"))
      (node (ref "U2") (pin "46") (pinfunction "GND_46") (pintype "power_in"))
      (node (ref "U2") (pin "53") (pinfunction "GND_53") (pintype "power_in"))
      (node (ref "U20") (pin "3") (pinfunction "D0_3") (pintype "input"))
      (node (ref "U20") (pin "4") (pinfunction "D1_4") (pintype "input"))
      (node (ref "U20") (pin "5") (pinfunction "D2_5") (pintype "input"))
      (node (ref "U20") (pin "6") (pinfunction "D3_6") (pintype "input"))
      (node (ref "U21") (pin "3") (pinfunction "D0_3") (pintype "input"))
      (node (ref "U21") (pin "4") (pinfunction "D1_4") (pintype "input"))
      (node (ref "U21") (pin "5") (pinfunction "D2_5") (pintype "input"))
      (node (ref "U21") (pin "6") (pinfunction "D3_6") (pintype "input"))
      (node (ref "U22") (pin "13") (pinfunction "OE_13") (pintype "input"))
      (node (ref "U23") (pin "13") (pinfunction "OE_13") (pintype "input"))
      (node (ref "U24") (pin "13") (pinfunction "OE_13") (pintype "input"))
      (node (ref "U25") (pin "13") (pinfunction "OE_13") (pintype "input"))
      (node (ref "U3") (pin "11") (pinfunction "GND_11") (pintype "power_in"))
      (node (ref "U3") (pin "18") (pinfunction "GND_18") (pintype "power_in"))
      (node (ref "U3") (pin "25") (pinfunction "GND_25") (pintype "power_in"))
      (node (ref "U3") (pin "32") (pinfunction "GND_32") (pintype "power_in"))
      (node (ref "U3") (pin "39") (pinfunction "GND_39") (pintype "power_in"))
      (node (ref "U3") (pin "4") (pinfunction "GND_4") (pintype "power_in"))
      (node (ref "U3") (pin "46") (pinfunction "GND_46") (pintype "power_in"))
      (node (ref "U3") (pin "53") (pinfunction "GND_53") (pintype "power_in"))
      (node (ref "U32") (pin "1") (pinfunction "A_1") (pintype "input"))
      (node (ref "U4") (pin "11") (pinfunction "GND_11") (pintype "power_in"))
      (node (ref "U4") (pin "18") (pinfunction "GND_18") (pintype "power_in"))
      (node (ref "U4") (pin "25") (pinfunction "GND_25") (pintype "power_in"))
      (node (ref "U4") (pin "32") (pinfunction "GND_32") (pintype "power_in"))
      (node (ref "U4") (pin "39") (pinfunction "GND_39") (pintype "power_in"))
      (node (ref "U4") (pin "4") (pinfunction "GND_4") (pintype "power_in"))
      (node (ref "U4") (pin "46") (pinfunction "GND_46") (pintype "power_in"))
      (node (ref "U4") (pin "53") (pinfunction "GND_53") (pintype "power_in"))
      (node (ref "U5") (pin "3") (pinfunction "D0_3") (pintype "input"))
      (node (ref "U5") (pin "4") (pinfunction "D1_4") (pintype "input"))
      (node (ref "U5") (pin "5") (pinfunction "D2_5") (pintype "input"))
      (node (ref "U5") (pin "6") (pinfunction "D3_6") (pintype "input"))
      (node (ref "U6") (pin "3") (pinfunction "D0_3") (pintype "input"))
      (node (ref "U6") (pin "4") (pinfunction "D1_4") (pintype "input"))
      (node (ref "U6") (pin "5") (pinfunction "D2_5") (pintype "input"))
      (node (ref "U6") (pin "6") (pinfunction "D3_6") (pintype "input"))
      (node (ref "U7") (pin "3") (pinfunction "J_3") (pintype "input"))
      (node (ref "X1") (pin "2") (pinfunction "GND_2") (pintype "power_in"))
      (node (ref "X2") (pin "1") (pinfunction "K_1") (pintype "passive"))
    )
    (net (code "54") (name "HB_L") (class "Default")
      (node (ref "U13") (pin "2") (pinfunction "B_2") (pintype "input"))
      (node (ref "U30") (pin "6") (pinfunction "Q_6") (pintype "output"))
    )
    (net (code "55") (name "HS") (class "Default")
      (node (ref "IC7") (pin "20") (pinfunction "I/O6_20") (pintype "bidirectional"))
      (node (ref "U29") (pin "2") (pinfunction "J_2") (pintype "input"))
    )
    (net (code "56") (name "HSYNC") (class "Default")
      (node (ref "J1") (pin "13") (pinfunction "HSYNC_13") (pintype "passive"))
      (node (ref "U29") (pin "6") (pinfunction "Q_6") (pintype "output"))
    )
    (net (code "57") (name "H_BLANK") (class "Default")
      (node (ref "IC7") (pin "17") (pinfunction "I/O3_17") (pintype "bidirectional"))
      (node (ref "U30") (pin "2") (pinfunction "J_2") (pintype "input"))
    )
    (net (code "58") (name "M1_~{R}{slash}W") (class "Default")
      (node (ref "SRAM1") (pin "37") (pinfunction "OE_37") (pintype "input"))
      (node (ref "U10") (pin "19") (pinfunction "OE_19") (pintype "input"))
      (node (ref "U2") (pin "1") (pinfunction "1OE1_1") (pintype "input"))
      (node (ref "U2") (pin "28") (pinfunction "2OE1_28") (pintype "input"))
      (node (ref "U2") (pin "29") (pinfunction "2OE2_29") (pintype "input"))
      (node (ref "U2") (pin "56") (pinfunction "1OE2_56") (pintype "input"))
      (node (ref "U27") (pin "1") (pinfunction "B_1") (pintype "input"))
      (node (ref "U28") (pin "5") (pinfunction "Q_5") (pintype "output"))
      (node (ref "U3") (pin "1") (pinfunction "1OE1_1") (pintype "input"))
      (node (ref "U3") (pin "28") (pinfunction "2OE1_28") (pintype "input"))
      (node (ref "U3") (pin "29") (pinfunction "2OE2_29") (pintype "input"))
      (node (ref "U3") (pin "56") (pinfunction "1OE2_56") (pintype "input"))
      (node (ref "U9") (pin "19") (pinfunction "OE_19") (pintype "input"))
    )
    (net (code "59") (name "M2_~{R}{slash}W") (class "Default")
      (node (ref "SRAM2") (pin "37") (pinfunction "OE_37") (pintype "input"))
      (node (ref "U1") (pin "1") (pinfunction "1OE1_1") (pintype "input"))
      (node (ref "U1") (pin "28") (pinfunction "2OE1_28") (pintype "input"))
      (node (ref "U1") (pin "29") (pinfunction "2OE2_29") (pintype "input"))
      (node (ref "U1") (pin "56") (pinfunction "1OE2_56") (pintype "input"))
      (node (ref "U11") (pin "19") (pinfunction "OE_19") (pintype "input"))
      (node (ref "U28") (pin "6") (pinfunction "~{Q}_6") (pintype "output"))
      (node (ref "U31") (pin "1") (pinfunction "B_1") (pintype "input"))
      (node (ref "U4") (pin "1") (pinfunction "1OE1_1") (pintype "input"))
      (node (ref "U4") (pin "28") (pinfunction "2OE1_28") (pintype "input"))
      (node (ref "U4") (pin "29") (pinfunction "2OE2_29") (pintype "input"))
      (node (ref "U4") (pin "56") (pinfunction "1OE2_56") (pintype "input"))
      (node (ref "U8") (pin "19") (pinfunction "OE_19") (pintype "input"))
    )
    (net (code "60") (name "MEM1_A0") (class "Default")
      (node (ref "SRAM1") (pin "3") (pinfunction "A0_3") (pintype "input"))
      (node (ref "U1") (pin "27") (pinfunction "2Y10_27") (pintype "output"))
      (node (ref "U2") (pin "2") (pinfunction "1Y1_2") (pintype "output"))
    )
    (net (code "61") (name "MEM1_A1") (class "Default")
      (node (ref "SRAM1") (pin "4") (pinfunction "A1_4") (pintype "input"))
      (node (ref "U1") (pin "26") (pinfunction "2Y9_26") (pintype "output"))
      (node (ref "U2") (pin "3") (pinfunction "1Y2_3") (pintype "output"))
    )
    (net (code "62") (name "MEM1_A2") (class "Default")
      (node (ref "SRAM1") (pin "5") (pinfunction "A2_5") (pintype "input"))
      (node (ref "U1") (pin "24") (pinfunction "2Y8_24") (pintype "output"))
      (node (ref "U2") (pin "5") (pinfunction "1Y3_5") (pintype "output"))
    )
    (net (code "63") (name "MEM1_A3") (class "Default")
      (node (ref "SRAM1") (pin "6") (pinfunction "A3_6") (pintype "input"))
      (node (ref "U1") (pin "23") (pinfunction "2Y7_23") (pintype "output"))
      (node (ref "U2") (pin "6") (pinfunction "1Y4_6") (pintype "output"))
    )
    (net (code "64") (name "MEM1_A4") (class "Default")
      (node (ref "SRAM1") (pin "7") (pinfunction "A4_7") (pintype "input"))
      (node (ref "U1") (pin "21") (pinfunction "2Y6_21") (pintype "output"))
      (node (ref "U2") (pin "8") (pinfunction "1Y5_8") (pintype "output"))
    )
    (net (code "65") (name "MEM1_A5") (class "Default")
      (node (ref "SRAM1") (pin "16") (pinfunction "A5_16") (pintype "input"))
      (node (ref "U1") (pin "20") (pinfunction "2Y5_20") (pintype "output"))
      (node (ref "U2") (pin "9") (pinfunction "1Y6_9") (pintype "output"))
    )
    (net (code "66") (name "MEM1_A6") (class "Default")
      (node (ref "SRAM1") (pin "17") (pinfunction "A6_17") (pintype "input"))
      (node (ref "U1") (pin "19") (pinfunction "2Y4_19") (pintype "output"))
      (node (ref "U2") (pin "10") (pinfunction "1Y7_10") (pintype "output"))
    )
    (net (code "67") (name "MEM1_A7") (class "Default")
      (node (ref "SRAM1") (pin "18") (pinfunction "A7_18") (pintype "input"))
      (node (ref "U1") (pin "17") (pinfunction "2Y3_17") (pintype "output"))
      (node (ref "U2") (pin "12") (pinfunction "1Y8_12") (pintype "output"))
    )
    (net (code "68") (name "MEM1_A8") (class "Default")
      (node (ref "SRAM1") (pin "19") (pinfunction "A8_19") (pintype "input"))
      (node (ref "U1") (pin "16") (pinfunction "2Y2_16") (pintype "output"))
      (node (ref "U2") (pin "13") (pinfunction "1Y9_13") (pintype "output"))
    )
    (net (code "69") (name "MEM1_A9") (class "Default")
      (node (ref "SRAM1") (pin "20") (pinfunction "A9_20") (pintype "input"))
      (node (ref "U1") (pin "15") (pinfunction "2Y1_15") (pintype "output"))
      (node (ref "U2") (pin "14") (pinfunction "1Y10_14") (pintype "output"))
    )
    (net (code "70") (name "MEM1_A10") (class "Default")
      (node (ref "SRAM1") (pin "26") (pinfunction "A10_26") (pintype "input"))
      (node (ref "U1") (pin "14") (pinfunction "1Y10_14") (pintype "output"))
      (node (ref "U2") (pin "15") (pinfunction "2Y1_15") (pintype "output"))
    )
    (net (code "71") (name "MEM1_A11") (class "Default")
      (node (ref "SRAM1") (pin "27") (pinfunction "A11_27") (pintype "input"))
      (node (ref "U1") (pin "13") (pinfunction "1Y9_13") (pintype "output"))
      (node (ref "U2") (pin "16") (pinfunction "2Y2_16") (pintype "output"))
    )
    (net (code "72") (name "MEM1_A12") (class "Default")
      (node (ref "SRAM1") (pin "28") (pinfunction "A12_28") (pintype "input"))
      (node (ref "U1") (pin "12") (pinfunction "1Y8_12") (pintype "output"))
      (node (ref "U2") (pin "17") (pinfunction "2Y3_17") (pintype "output"))
    )
    (net (code "73") (name "MEM1_A13") (class "Default")
      (node (ref "SRAM1") (pin "29") (pinfunction "A13_29") (pintype "input"))
      (node (ref "U1") (pin "10") (pinfunction "1Y7_10") (pintype "output"))
      (node (ref "U2") (pin "19") (pinfunction "2Y4_19") (pintype "output"))
    )
    (net (code "74") (name "MEM1_A14") (class "Default")
      (node (ref "SRAM1") (pin "30") (pinfunction "A14_30") (pintype "input"))
      (node (ref "U1") (pin "9") (pinfunction "1Y6_9") (pintype "output"))
      (node (ref "U2") (pin "20") (pinfunction "2Y5_20") (pintype "output"))
    )
    (net (code "75") (name "MEM1_A15") (class "Default")
      (node (ref "SRAM1") (pin "38") (pinfunction "A15_38") (pintype "input"))
      (node (ref "U1") (pin "8") (pinfunction "1Y5_8") (pintype "output"))
      (node (ref "U2") (pin "21") (pinfunction "2Y6_21") (pintype "output"))
    )
    (net (code "76") (name "MEM1_A16") (class "Default")
      (node (ref "SRAM1") (pin "39") (pinfunction "A16_39") (pintype "input"))
      (node (ref "U1") (pin "6") (pinfunction "1Y4_6") (pintype "output"))
      (node (ref "U2") (pin "23") (pinfunction "2Y7_23") (pintype "output"))
    )
    (net (code "77") (name "MEM1_A17") (class "Default")
      (node (ref "SRAM1") (pin "40") (pinfunction "A17_40") (pintype "input"))
      (node (ref "U1") (pin "5") (pinfunction "1Y3_5") (pintype "output"))
      (node (ref "U2") (pin "24") (pinfunction "2Y8_24") (pintype "output"))
    )
    (net (code "78") (name "MEM1_A18") (class "Default")
      (node (ref "SRAM1") (pin "41") (pinfunction "A18_41") (pintype "input"))
      (node (ref "U1") (pin "3") (pinfunction "1Y2_3") (pintype "output"))
      (node (ref "U2") (pin "26") (pinfunction "2Y9_26") (pintype "output"))
    )
    (net (code "79") (name "MEM1_A19") (class "Default")
      (node (ref "SRAM1") (pin "25") (pinfunction "A19_25") (pintype "input"))
      (node (ref "U1") (pin "2") (pinfunction "1Y1_2") (pintype "output"))
      (node (ref "U2") (pin "27") (pinfunction "2Y10_27") (pintype "output"))
    )
    (net (code "80") (name "MEM1_D0") (class "Default")
      (node (ref "SRAM1") (pin "9") (pinfunction "I/O00_9") (pintype "bidirectional"))
      (node (ref "U10") (pin "9") (pinfunction "A8_9") (pintype "input"))
      (node (ref "U8") (pin "11") (pinfunction "B8_11") (pintype "output"))
    )
    (net (code "81") (name "MEM1_D1") (class "Default")
      (node (ref "SRAM1") (pin "10") (pinfunction "I/O01_10") (pintype "bidirectional"))
      (node (ref "U10") (pin "8") (pinfunction "A7_8") (pintype "input"))
      (node (ref "U8") (pin "12") (pinfunction "B7_12") (pintype "output"))
    )
    (net (code "82") (name "MEM1_D2") (class "Default")
      (node (ref "SRAM1") (pin "13") (pinfunction "I/O02_13") (pintype "bidirectional"))
      (node (ref "U10") (pin "7") (pinfunction "A6_7") (pintype "input"))
      (node (ref "U8") (pin "13") (pinfunction "B6_13") (pintype "output"))
    )
    (net (code "83") (name "MEM1_D3") (class "Default")
      (node (ref "SRAM1") (pin "14") (pinfunction "I/O03_14") (pintype "bidirectional"))
      (node (ref "U10") (pin "6") (pinfunction "A5_6") (pintype "input"))
      (node (ref "U8") (pin "14") (pinfunction "B5_14") (pintype "output"))
    )
    (net (code "84") (name "MEM1_D4") (class "Default")
      (node (ref "SRAM1") (pin "31") (pinfunction "I/O04_31") (pintype "bidirectional"))
      (node (ref "U10") (pin "5") (pinfunction "A4_5") (pintype "input"))
      (node (ref "U8") (pin "15") (pinfunction "B4_15") (pintype "output"))
    )
    (net (code "85") (name "MEM1_D5") (class "Default")
      (node (ref "SRAM1") (pin "32") (pinfunction "I/O05_32") (pintype "bidirectional"))
      (node (ref "U10") (pin "4") (pinfunction "A3_4") (pintype "input"))
      (node (ref "U8") (pin "16") (pinfunction "B3_16") (pintype "output"))
    )
    (net (code "86") (name "MEM1_D6") (class "Default")
      (node (ref "SRAM1") (pin "35") (pinfunction "I/O06_35") (pintype "bidirectional"))
      (node (ref "U10") (pin "3") (pinfunction "A2_3") (pintype "input"))
      (node (ref "U8") (pin "17") (pinfunction "B2_17") (pintype "output"))
    )
    (net (code "87") (name "MEM1_D7") (class "Default")
      (node (ref "SRAM1") (pin "36") (pinfunction "I/O07_36") (pintype "bidirectional"))
      (node (ref "U10") (pin "2") (pinfunction "A1_2") (pintype "input"))
      (node (ref "U8") (pin "18") (pinfunction "B1_18") (pintype "output"))
    )
    (net (code "88") (name "MEM2_A0") (class "Default")
      (node (ref "SRAM2") (pin "3") (pinfunction "A0_3") (pintype "input"))
      (node (ref "U3") (pin "2") (pinfunction "1Y1_2") (pintype "output"))
      (node (ref "U4") (pin "27") (pinfunction "2Y10_27") (pintype "output"))
    )
    (net (code "89") (name "MEM2_A1") (class "Default")
      (node (ref "SRAM2") (pin "4") (pinfunction "A1_4") (pintype "input"))
      (node (ref "U3") (pin "3") (pinfunction "1Y2_3") (pintype "output"))
      (node (ref "U4") (pin "26") (pinfunction "2Y9_26") (pintype "output"))
    )
    (net (code "90") (name "MEM2_A2") (class "Default")
      (node (ref "SRAM2") (pin "5") (pinfunction "A2_5") (pintype "input"))
      (node (ref "U3") (pin "5") (pinfunction "1Y3_5") (pintype "output"))
      (node (ref "U4") (pin "24") (pinfunction "2Y8_24") (pintype "output"))
    )
    (net (code "91") (name "MEM2_A3") (class "Default")
      (node (ref "SRAM2") (pin "6") (pinfunction "A3_6") (pintype "input"))
      (node (ref "U3") (pin "6") (pinfunction "1Y4_6") (pintype "output"))
      (node (ref "U4") (pin "23") (pinfunction "2Y7_23") (pintype "output"))
    )
    (net (code "92") (name "MEM2_A4") (class "Default")
      (node (ref "SRAM2") (pin "7") (pinfunction "A4_7") (pintype "input"))
      (node (ref "U3") (pin "8") (pinfunction "1Y5_8") (pintype "output"))
      (node (ref "U4") (pin "21") (pinfunction "2Y6_21") (pintype "output"))
    )
    (net (code "93") (name "MEM2_A5") (class "Default")
      (node (ref "SRAM2") (pin "16") (pinfunction "A5_16") (pintype "input"))
      (node (ref "U3") (pin "9") (pinfunction "1Y6_9") (pintype "output"))
      (node (ref "U4") (pin "20") (pinfunction "2Y5_20") (pintype "output"))
    )
    (net (code "94") (name "MEM2_A6") (class "Default")
      (node (ref "SRAM2") (pin "17") (pinfunction "A6_17") (pintype "input"))
      (node (ref "U3") (pin "10") (pinfunction "1Y7_10") (pintype "output"))
      (node (ref "U4") (pin "19") (pinfunction "2Y4_19") (pintype "output"))
    )
    (net (code "95") (name "MEM2_A7") (class "Default")
      (node (ref "SRAM2") (pin "18") (pinfunction "A7_18") (pintype "input"))
      (node (ref "U3") (pin "12") (pinfunction "1Y8_12") (pintype "output"))
      (node (ref "U4") (pin "17") (pinfunction "2Y3_17") (pintype "output"))
    )
    (net (code "96") (name "MEM2_A8") (class "Default")
      (node (ref "SRAM2") (pin "19") (pinfunction "A8_19") (pintype "input"))
      (node (ref "U3") (pin "13") (pinfunction "1Y9_13") (pintype "output"))
      (node (ref "U4") (pin "16") (pinfunction "2Y2_16") (pintype "output"))
    )
    (net (code "97") (name "MEM2_A9") (class "Default")
      (node (ref "SRAM2") (pin "20") (pinfunction "A9_20") (pintype "input"))
      (node (ref "U3") (pin "14") (pinfunction "1Y10_14") (pintype "output"))
      (node (ref "U4") (pin "15") (pinfunction "2Y1_15") (pintype "output"))
    )
    (net (code "98") (name "MEM2_A10") (class "Default")
      (node (ref "SRAM2") (pin "26") (pinfunction "A10_26") (pintype "input"))
      (node (ref "U3") (pin "15") (pinfunction "2Y1_15") (pintype "output"))
      (node (ref "U4") (pin "14") (pinfunction "1Y10_14") (pintype "output"))
    )
    (net (code "99") (name "MEM2_A11") (class "Default")
      (node (ref "SRAM2") (pin "27") (pinfunction "A11_27") (pintype "input"))
      (node (ref "U3") (pin "16") (pinfunction "2Y2_16") (pintype "output"))
      (node (ref "U4") (pin "13") (pinfunction "1Y9_13") (pintype "output"))
    )
    (net (code "100") (name "MEM2_A12") (class "Default")
      (node (ref "SRAM2") (pin "28") (pinfunction "A12_28") (pintype "input"))
      (node (ref "U3") (pin "17") (pinfunction "2Y3_17") (pintype "output"))
      (node (ref "U4") (pin "12") (pinfunction "1Y8_12") (pintype "output"))
    )
    (net (code "101") (name "MEM2_A13") (class "Default")
      (node (ref "SRAM2") (pin "29") (pinfunction "A13_29") (pintype "input"))
      (node (ref "U3") (pin "19") (pinfunction "2Y4_19") (pintype "output"))
      (node (ref "U4") (pin "10") (pinfunction "1Y7_10") (pintype "output"))
    )
    (net (code "102") (name "MEM2_A14") (class "Default")
      (node (ref "SRAM2") (pin "30") (pinfunction "A14_30") (pintype "input"))
      (node (ref "U3") (pin "20") (pinfunction "2Y5_20") (pintype "output"))
      (node (ref "U4") (pin "9") (pinfunction "1Y6_9") (pintype "output"))
    )
    (net (code "103") (name "MEM2_A15") (class "Default")
      (node (ref "SRAM2") (pin "38") (pinfunction "A15_38") (pintype "input"))
      (node (ref "U3") (pin "21") (pinfunction "2Y6_21") (pintype "output"))
      (node (ref "U4") (pin "8") (pinfunction "1Y5_8") (pintype "output"))
    )
    (net (code "104") (name "MEM2_A16") (class "Default")
      (node (ref "SRAM2") (pin "39") (pinfunction "A16_39") (pintype "input"))
      (node (ref "U3") (pin "23") (pinfunction "2Y7_23") (pintype "output"))
      (node (ref "U4") (pin "6") (pinfunction "1Y4_6") (pintype "output"))
    )
    (net (code "105") (name "MEM2_A17") (class "Default")
      (node (ref "SRAM2") (pin "40") (pinfunction "A17_40") (pintype "input"))
      (node (ref "U3") (pin "24") (pinfunction "2Y8_24") (pintype "output"))
      (node (ref "U4") (pin "5") (pinfunction "1Y3_5") (pintype "output"))
    )
    (net (code "106") (name "MEM2_A18") (class "Default")
      (node (ref "SRAM2") (pin "41") (pinfunction "A18_41") (pintype "input"))
      (node (ref "U3") (pin "26") (pinfunction "2Y9_26") (pintype "output"))
      (node (ref "U4") (pin "3") (pinfunction "1Y2_3") (pintype "output"))
    )
    (net (code "107") (name "MEM2_A19") (class "Default")
      (node (ref "SRAM2") (pin "25") (pinfunction "A19_25") (pintype "input"))
      (node (ref "U3") (pin "27") (pinfunction "2Y10_27") (pintype "output"))
      (node (ref "U4") (pin "2") (pinfunction "1Y1_2") (pintype "output"))
    )
    (net (code "108") (name "MEM2_D0") (class "Default")
      (node (ref "SRAM2") (pin "9") (pinfunction "I/O00_9") (pintype "bidirectional"))
      (node (ref "U11") (pin "2") (pinfunction "A1_2") (pintype "input"))
      (node (ref "U9") (pin "18") (pinfunction "B1_18") (pintype "output"))
    )
    (net (code "109") (name "MEM2_D1") (class "Default")
      (node (ref "SRAM2") (pin "10") (pinfunction "I/O01_10") (pintype "bidirectional"))
      (node (ref "U11") (pin "3") (pinfunction "A2_3") (pintype "input"))
      (node (ref "U9") (pin "17") (pinfunction "B2_17") (pintype "output"))
    )
    (net (code "110") (name "MEM2_D2") (class "Default")
      (node (ref "SRAM2") (pin "13") (pinfunction "I/O02_13") (pintype "bidirectional"))
      (node (ref "U11") (pin "4") (pinfunction "A3_4") (pintype "input"))
      (node (ref "U9") (pin "16") (pinfunction "B3_16") (pintype "output"))
    )
    (net (code "111") (name "MEM2_D3") (class "Default")
      (node (ref "SRAM2") (pin "14") (pinfunction "I/O03_14") (pintype "bidirectional"))
      (node (ref "U11") (pin "5") (pinfunction "A4_5") (pintype "input"))
      (node (ref "U9") (pin "15") (pinfunction "B4_15") (pintype "output"))
    )
    (net (code "112") (name "MEM2_D4") (class "Default")
      (node (ref "SRAM2") (pin "31") (pinfunction "I/O04_31") (pintype "bidirectional"))
      (node (ref "U11") (pin "6") (pinfunction "A5_6") (pintype "input"))
      (node (ref "U9") (pin "14") (pinfunction "B5_14") (pintype "output"))
    )
    (net (code "113") (name "MEM2_D5") (class "Default")
      (node (ref "SRAM2") (pin "32") (pinfunction "I/O05_32") (pintype "bidirectional"))
      (node (ref "U11") (pin "7") (pinfunction "A6_7") (pintype "input"))
      (node (ref "U9") (pin "13") (pinfunction "B6_13") (pintype "output"))
    )
    (net (code "114") (name "MEM2_D6") (class "Default")
      (node (ref "SRAM2") (pin "35") (pinfunction "I/O06_35") (pintype "bidirectional"))
      (node (ref "U11") (pin "8") (pinfunction "A7_8") (pintype "input"))
      (node (ref "U9") (pin "12") (pinfunction "B7_12") (pintype "output"))
    )
    (net (code "115") (name "MEM2_D7") (class "Default")
      (node (ref "SRAM2") (pin "36") (pinfunction "I/O07_36") (pintype "bidirectional"))
      (node (ref "U11") (pin "9") (pinfunction "A8_9") (pintype "input"))
      (node (ref "U9") (pin "11") (pinfunction "B8_11") (pintype "output"))
    )
    (net (code "116") (name "MOSI") (class "Default")
      (node (ref "LPC1769") (pin "11") (pinfunction "11_11") (pintype "passive"))
      (node (ref "U22") (pin "14") (pinfunction "DS_14") (pintype "input"))
    )
    (net (code "117") (name "Net-(ADV7125-COMP)") (class "Default")
      (node (ref "ADV7125") (pin "35") (pinfunction "COMP_35") (pintype "passive"))
      (node (ref "C1") (pin "1") (pinfunction "1_1") (pintype "passive"))
    )
    (net (code "118") (name "Net-(ADV7125-RSET)") (class "Default")
      (node (ref "ADV7125") (pin "37") (pinfunction "RSET_37") (pintype "input"))
      (node (ref "R1") (pin "2") (pinfunction "2_2") (pintype "passive"))
    )
    (net (code "119") (name "Net-(ADV7125-VREF)") (class "Default")
      (node (ref "ADV7125") (pin "36") (pinfunction "VREF_36") (pintype "input"))
      (node (ref "C91") (pin "2") (pinfunction "2_2") (pintype "passive"))
      (node (ref "D1") (pin "1") (pinfunction "V+_1") (pintype "passive"))
      (node (ref "R8") (pin "1") (pinfunction "1_1") (pintype "passive"))
    )
    (net (code "120") (name "Net-(C88-Pad2)") (class "Default")
      (node (ref "C88") (pin "2") (pinfunction "2_2") (pintype "passive"))
      (node (ref "R5") (pin "1") (pinfunction "1_1") (pintype "passive"))
    )
    (net (code "121") (name "Net-(C89-Pad2)") (class "Default")
      (node (ref "C89") (pin "2") (pinfunction "2_2") (pintype "passive"))
      (node (ref "R9") (pin "1") (pinfunction "1_1") (pintype "passive"))
    )
    (net (code "122") (name "Net-(C90-Pad2)") (class "Default")
      (node (ref "C90") (pin "2") (pinfunction "2_2") (pintype "passive"))
      (node (ref "R10") (pin "2") (pinfunction "2_2") (pintype "passive"))
    )
    (net (code "123") (name "Net-(C102-Pad2)") (class "Default")
      (node (ref "C102") (pin "2") (pinfunction "2_2") (pintype "passive"))
      (node (ref "R11") (pin "1") (pinfunction "1_1") (pintype "passive"))
    )
    (net (code "124") (name "Net-(D2-PadC)") (class "Default")
      (node (ref "D2") (pin "C") (pinfunction "C_C") (pintype "passive"))
      (node (ref "R12") (pin "1") (pinfunction "1_1") (pintype "passive"))
    )
    (net (code "125") (name "Net-(IC6A-CLK{slash}I0)") (class "Default")
      (node (ref "IC6") (pin "1") (pinfunction "CLK/I0_1") (pintype "input"))
      (node (ref "U19") (pin "14") (pinfunction "Q0_14") (pintype "output"))
    )
    (net (code "126") (name "Net-(IC6A-I1)") (class "Default")
      (node (ref "IC6") (pin "2") (pinfunction "I1_2") (pintype "input"))
      (node (ref "U19") (pin "13") (pinfunction "Q1_13") (pintype "output"))
    )
    (net (code "127") (name "Net-(IC6A-I2)") (class "Default")
      (node (ref "IC6") (pin "3") (pinfunction "I2_3") (pintype "input"))
      (node (ref "U19") (pin "12") (pinfunction "Q2_12") (pintype "output"))
    )
    (net (code "128") (name "Net-(IC6A-I3)") (class "Default")
      (node (ref "IC6") (pin "4") (pinfunction "I3_4") (pintype "input"))
      (node (ref "U19") (pin "11") (pinfunction "Q3_11") (pintype "output"))
    )
    (net (code "129") (name "Net-(IC6A-I4)") (class "Default")
      (node (ref "IC6") (pin "5") (pinfunction "I4_5") (pintype "input"))
      (node (ref "U20") (pin "14") (pinfunction "Q0_14") (pintype "output"))
    )
    (net (code "130") (name "Net-(IC6A-I5)") (class "Default")
      (node (ref "IC6") (pin "6") (pinfunction "I5_6") (pintype "input"))
      (node (ref "U20") (pin "13") (pinfunction "Q1_13") (pintype "output"))
    )
    (net (code "131") (name "Net-(IC6A-I6)") (class "Default")
      (node (ref "IC6") (pin "7") (pinfunction "I6_7") (pintype "input"))
      (node (ref "U20") (pin "12") (pinfunction "Q2_12") (pintype "output"))
    )
    (net (code "132") (name "Net-(IC6A-I7)") (class "Default")
      (node (ref "IC6") (pin "8") (pinfunction "I7_8") (pintype "input"))
      (node (ref "U20") (pin "11") (pinfunction "Q3_11") (pintype "output"))
    )
    (net (code "133") (name "Net-(IC6A-I8)") (class "Default")
      (node (ref "IC6") (pin "9") (pinfunction "I8_9") (pintype "input"))
      (node (ref "U21") (pin "14") (pinfunction "Q0_14") (pintype "output"))
    )
    (net (code "134") (name "Net-(IC6A-I9)") (class "Default")
      (node (ref "IC6") (pin "10") (pinfunction "I9_10") (pintype "input"))
      (node (ref "U21") (pin "13") (pinfunction "Q1_13") (pintype "output"))
    )
    (net (code "135") (name "Net-(IC7A-CLK{slash}I0)") (class "Default")
      (node (ref "IC7") (pin "1") (pinfunction "CLK/I0_1") (pintype "input"))
      (node (ref "U6") (pin "14") (pinfunction "Q0_14") (pintype "output"))
    )
    (net (code "136") (name "Net-(IC7A-I1)") (class "Default")
      (node (ref "IC7") (pin "2") (pinfunction "I1_2") (pintype "input"))
      (node (ref "U6") (pin "13") (pinfunction "Q1_13") (pintype "output"))
    )
    (net (code "137") (name "Net-(IC7A-I2)") (class "Default")
      (node (ref "IC7") (pin "3") (pinfunction "I2_3") (pintype "input"))
      (node (ref "U6") (pin "12") (pinfunction "Q2_12") (pintype "output"))
    )
    (net (code "138") (name "Net-(IC7A-I3)") (class "Default")
      (node (ref "IC7") (pin "4") (pinfunction "I3_4") (pintype "input"))
      (node (ref "U6") (pin "11") (pinfunction "Q3_11") (pintype "output"))
    )
    (net (code "139") (name "Net-(IC7A-I4)") (class "Default")
      (node (ref "IC7") (pin "5") (pinfunction "I4_5") (pintype "input"))
      (node (ref "U17") (pin "14") (pinfunction "Q0_14") (pintype "output"))
    )
    (net (code "140") (name "Net-(IC7A-I5)") (class "Default")
      (node (ref "IC7") (pin "6") (pinfunction "I5_6") (pintype "input"))
      (node (ref "U17") (pin "13") (pinfunction "Q1_13") (pintype "output"))
    )
    (net (code "141") (name "Net-(IC7A-I6)") (class "Default")
      (node (ref "IC7") (pin "7") (pinfunction "I6_7") (pintype "input"))
      (node (ref "U17") (pin "12") (pinfunction "Q2_12") (pintype "output"))
    )
    (net (code "142") (name "Net-(IC7A-I7)") (class "Default")
      (node (ref "IC7") (pin "8") (pinfunction "I7_8") (pintype "input"))
      (node (ref "U17") (pin "11") (pinfunction "Q3_11") (pintype "output"))
    )
    (net (code "143") (name "Net-(IC7A-I8)") (class "Default")
      (node (ref "IC7") (pin "9") (pinfunction "I8_9") (pintype "input"))
      (node (ref "U18") (pin "14") (pinfunction "Q0_14") (pintype "output"))
    )
    (net (code "144") (name "Net-(IC7A-I9)") (class "Default")
      (node (ref "IC7") (pin "10") (pinfunction "I9_10") (pintype "input"))
      (node (ref "U18") (pin "13") (pinfunction "Q1_13") (pintype "output"))
    )
    (net (code "145") (name "Net-(IC7A-I10)") (class "Default")
      (node (ref "IC7") (pin "11") (pinfunction "I10_11") (pintype "input"))
      (node (ref "U18") (pin "12") (pinfunction "Q2_12") (pintype "output"))
    )
    (net (code "146") (name "Net-(IC7A-I11)") (class "Default")
      (node (ref "IC7") (pin "13") (pinfunction "I11_13") (pintype "input"))
      (node (ref "U18") (pin "11") (pinfunction "Q3_11") (pintype "output"))
    )
    (net (code "147") (name "Net-(U12A-CEP)") (class "Default")
      (node (ref "U12") (pin "10") (pinfunction "CET_10") (pintype "input"))
      (node (ref "U12") (pin "7") (pinfunction "CEP_7") (pintype "input"))
      (node (ref "U5") (pin "15") (pinfunction "TC_15") (pintype "output"))
    )
    (net (code "148") (name "Net-(U12A-TC)") (class "Default")
      (node (ref "U12") (pin "15") (pinfunction "TC_15") (pintype "output"))
      (node (ref "U14") (pin "10") (pinfunction "CET_10") (pintype "input"))
      (node (ref "U14") (pin "7") (pinfunction "CEP_7") (pintype "input"))
    )
    (net (code "149") (name "Net-(U14A-TC)") (class "Default")
      (node (ref "U14") (pin "15") (pinfunction "TC_15") (pintype "output"))
      (node (ref "U15") (pin "10") (pinfunction "CET_10") (pintype "input"))
      (node (ref "U15") (pin "7") (pinfunction "CEP_7") (pintype "input"))
    )
    (net (code "150") (name "Net-(U15A-TC)") (class "Default")
      (node (ref "U15") (pin "15") (pinfunction "TC_15") (pintype "output"))
      (node (ref "U16") (pin "10") (pinfunction "CET_10") (pintype "input"))
      (node (ref "U16") (pin "7") (pinfunction "CEP_7") (pintype "input"))
    )
    (net (code "151") (name "Net-(U17A-CEP)") (class "Default")
      (node (ref "U17") (pin "10") (pinfunction "CET_10") (pintype "input"))
      (node (ref "U17") (pin "7") (pinfunction "CEP_7") (pintype "input"))
      (node (ref "U6") (pin "15") (pinfunction "TC_15") (pintype "output"))
    )
    (net (code "152") (name "Net-(U17A-TC)") (class "Default")
      (node (ref "U17") (pin "15") (pinfunction "TC_15") (pintype "output"))
      (node (ref "U18") (pin "10") (pinfunction "CET_10") (pintype "input"))
      (node (ref "U18") (pin "7") (pinfunction "CEP_7") (pintype "input"))
    )
    (net (code "153") (name "Net-(U19A-TC)") (class "Default")
      (node (ref "U19") (pin "15") (pinfunction "TC_15") (pintype "output"))
      (node (ref "U20") (pin "10") (pinfunction "CET_10") (pintype "input"))
      (node (ref "U20") (pin "7") (pinfunction "CEP_7") (pintype "input"))
    )
    (net (code "154") (name "Net-(U20A-TC)") (class "Default")
      (node (ref "U20") (pin "15") (pinfunction "TC_15") (pintype "output"))
      (node (ref "U21") (pin "10") (pinfunction "CET_10") (pintype "input"))
      (node (ref "U21") (pin "7") (pinfunction "CEP_7") (pintype "input"))
    )
    (net (code "155") (name "Net-(U22A-Q7S)") (class "Default")
      (node (ref "U22") (pin "9") (pinfunction "Q7S_9") (pintype "output"))
      (node (ref "U23") (pin "14") (pinfunction "DS_14") (pintype "input"))
    )
    (net (code "156") (name "Net-(U23A-Q7S)") (class "Default")
      (node (ref "U23") (pin "9") (pinfunction "Q7S_9") (pintype "output"))
      (node (ref "U24") (pin "14") (pinfunction "DS_14") (pintype "input"))
    )
    (net (code "157") (name "Net-(U24A-Q7S)") (class "Default")
      (node (ref "U24") (pin "9") (pinfunction "Q7S_9") (pintype "output"))
      (node (ref "U25") (pin "14") (pinfunction "DS_14") (pintype "input"))
    )
    (net (code "158") (name "Net-(U32A-Y)") (class "Default")
      (node (ref "U32") (pin "4") (pinfunction "Y_4") (pintype "output"))
      (node (ref "U7") (pin "4") (pinfunction "PRE_4") (pintype "input"))
    )
    (net (code "159") (name "Net-(X2C-K)") (class "Default")
      (node (ref "L2") (pin "1") (pinfunction "1_1") (pintype "passive"))
      (node (ref "X2") (pin "3") (pinfunction "K_3") (pintype "passive"))
    )
    (net (code "160") (name "PCLK_A0") (class "Default")
      (node (ref "U2") (pin "55") (pinfunction "1A1_55") (pintype "input"))
      (node (ref "U4") (pin "30") (pinfunction "2A10_30") (pintype "input"))
      (node (ref "U5") (pin "14") (pinfunction "Q0_14") (pintype "output"))
    )
    (net (code "161") (name "PCLK_A1") (class "Default")
      (node (ref "U2") (pin "54") (pinfunction "1A2_54") (pintype "input"))
      (node (ref "U4") (pin "31") (pinfunction "2A9_31") (pintype "input"))
      (node (ref "U5") (pin "13") (pinfunction "Q1_13") (pintype "output"))
    )
    (net (code "162") (name "PCLK_A2") (class "Default")
      (node (ref "U2") (pin "52") (pinfunction "1A3_52") (pintype "input"))
      (node (ref "U4") (pin "33") (pinfunction "2A8_33") (pintype "input"))
      (node (ref "U5") (pin "12") (pinfunction "Q2_12") (pintype "output"))
    )
    (net (code "163") (name "PCLK_A3") (class "Default")
      (node (ref "U2") (pin "51") (pinfunction "1A4_51") (pintype "input"))
      (node (ref "U4") (pin "34") (pinfunction "2A7_34") (pintype "input"))
      (node (ref "U5") (pin "11") (pinfunction "Q3_11") (pintype "output"))
    )
    (net (code "164") (name "PCLK_A4") (class "Default")
      (node (ref "U12") (pin "14") (pinfunction "Q0_14") (pintype "output"))
      (node (ref "U2") (pin "49") (pinfunction "1A5_49") (pintype "input"))
      (node (ref "U4") (pin "36") (pinfunction "2A6_36") (pintype "input"))
    )
    (net (code "165") (name "PCLK_A5") (class "Default")
      (node (ref "U12") (pin "13") (pinfunction "Q1_13") (pintype "output"))
      (node (ref "U2") (pin "48") (pinfunction "1A6_48") (pintype "input"))
      (node (ref "U4") (pin "37") (pinfunction "2A5_37") (pintype "input"))
    )
    (net (code "166") (name "PCLK_A6") (class "Default")
      (node (ref "U12") (pin "12") (pinfunction "Q2_12") (pintype "output"))
      (node (ref "U2") (pin "47") (pinfunction "1A7_47") (pintype "input"))
      (node (ref "U4") (pin "38") (pinfunction "2A4_38") (pintype "input"))
    )
    (net (code "167") (name "PCLK_A7") (class "Default")
      (node (ref "U12") (pin "11") (pinfunction "Q3_11") (pintype "output"))
      (node (ref "U2") (pin "45") (pinfunction "1A8_45") (pintype "input"))
      (node (ref "U4") (pin "40") (pinfunction "2A3_40") (pintype "input"))
    )
    (net (code "168") (name "PCLK_A8") (class "Default")
      (node (ref "U14") (pin "14") (pinfunction "Q0_14") (pintype "output"))
      (node (ref "U2") (pin "44") (pinfunction "1A9_44") (pintype "input"))
      (node (ref "U4") (pin "41") (pinfunction "2A2_41") (pintype "input"))
    )
    (net (code "169") (name "PCLK_A9") (class "Default")
      (node (ref "U14") (pin "13") (pinfunction "Q1_13") (pintype "output"))
      (node (ref "U2") (pin "43") (pinfunction "1A10_43") (pintype "input"))
      (node (ref "U4") (pin "42") (pinfunction "2A1_42") (pintype "input"))
    )
    (net (code "170") (name "PCLK_A10") (class "Default")
      (node (ref "U14") (pin "12") (pinfunction "Q2_12") (pintype "output"))
      (node (ref "U2") (pin "42") (pinfunction "2A1_42") (pintype "input"))
      (node (ref "U4") (pin "43") (pinfunction "1A10_43") (pintype "input"))
    )
    (net (code "171") (name "PCLK_A11") (class "Default")
      (node (ref "U14") (pin "11") (pinfunction "Q3_11") (pintype "output"))
      (node (ref "U2") (pin "41") (pinfunction "2A2_41") (pintype "input"))
      (node (ref "U4") (pin "44") (pinfunction "1A9_44") (pintype "input"))
    )
    (net (code "172") (name "PCLK_A12") (class "Default")
      (node (ref "U15") (pin "14") (pinfunction "Q0_14") (pintype "output"))
      (node (ref "U2") (pin "40") (pinfunction "2A3_40") (pintype "input"))
      (node (ref "U4") (pin "45") (pinfunction "1A8_45") (pintype "input"))
    )
    (net (code "173") (name "PCLK_A13") (class "Default")
      (node (ref "U15") (pin "13") (pinfunction "Q1_13") (pintype "output"))
      (node (ref "U2") (pin "38") (pinfunction "2A4_38") (pintype "input"))
      (node (ref "U4") (pin "47") (pinfunction "1A7_47") (pintype "input"))
    )
    (net (code "174") (name "PCLK_A14") (class "Default")
      (node (ref "U15") (pin "12") (pinfunction "Q2_12") (pintype "output"))
      (node (ref "U2") (pin "37") (pinfunction "2A5_37") (pintype "input"))
      (node (ref "U4") (pin "48") (pinfunction "1A6_48") (pintype "input"))
    )
    (net (code "175") (name "PCLK_A15") (class "Default")
      (node (ref "U15") (pin "11") (pinfunction "Q3_11") (pintype "output"))
      (node (ref "U2") (pin "36") (pinfunction "2A6_36") (pintype "input"))
      (node (ref "U4") (pin "49") (pinfunction "1A5_49") (pintype "input"))
    )
    (net (code "176") (name "PCLK_A16") (class "Default")
      (node (ref "U16") (pin "14") (pinfunction "Q0_14") (pintype "output"))
      (node (ref "U2") (pin "34") (pinfunction "2A7_34") (pintype "input"))
      (node (ref "U4") (pin "51") (pinfunction "1A4_51") (pintype "input"))
    )
    (net (code "177") (name "PCLK_A17") (class "Default")
      (node (ref "U16") (pin "13") (pinfunction "Q1_13") (pintype "output"))
      (node (ref "U2") (pin "33") (pinfunction "2A8_33") (pintype "input"))
      (node (ref "U4") (pin "52") (pinfunction "1A3_52") (pintype "input"))
    )
    (net (code "178") (name "PCLK_A18") (class "Default")
      (node (ref "U16") (pin "12") (pinfunction "Q2_12") (pintype "output"))
      (node (ref "U2") (pin "31") (pinfunction "2A9_31") (pintype "input"))
      (node (ref "U4") (pin "54") (pinfunction "1A2_54") (pintype "input"))
    )
    (net (code "179") (name "PCLK_A19") (class "Default")
      (node (ref "U16") (pin "11") (pinfunction "Q3_11") (pintype "output"))
      (node (ref "U2") (pin "30") (pinfunction "2A10_30") (pintype "input"))
      (node (ref "U4") (pin "55") (pinfunction "1A1_55") (pintype "input"))
    )
    (net (code "180") (name "R0") (class "Default")
      (node (ref "ADV7125") (pin "43") (pinfunction "R2_43") (pintype "input"))
      (node (ref "ADV7125") (pin "46") (pinfunction "R5_46") (pintype "input"))
      (node (ref "U10") (pin "16") (pinfunction "B3_16") (pintype "output"))
      (node (ref "U11") (pin "13") (pinfunction "B6_13") (pintype "output"))
    )
    (net (code "181") (name "R1") (class "Default")
      (node (ref "ADV7125") (pin "41") (pinfunction "R0_41") (pintype "input"))
      (node (ref "ADV7125") (pin "44") (pinfunction "R3_44") (pintype "input"))
      (node (ref "ADV7125") (pin "47") (pinfunction "R6_47") (pintype "input"))
      (node (ref "U10") (pin "17") (pinfunction "B2_17") (pintype "output"))
      (node (ref "U11") (pin "12") (pinfunction "B7_12") (pintype "output"))
    )
    (net (code "182") (name "R2") (class "Default")
      (node (ref "ADV7125") (pin "42") (pinfunction "R1_42") (pintype "input"))
      (node (ref "ADV7125") (pin "45") (pinfunction "R4_45") (pintype "input"))
      (node (ref "ADV7125") (pin "48") (pinfunction "R7_48") (pintype "input"))
      (node (ref "U10") (pin "18") (pinfunction "B1_18") (pintype "output"))
      (node (ref "U11") (pin "11") (pinfunction "B8_11") (pintype "output"))
    )
    (net (code "183") (name "RESET") (class "Default")
      (node (ref "U22") (pin "10") (pinfunction "MR_10") (pintype "input"))
      (node (ref "U23") (pin "10") (pinfunction "MR_10") (pintype "input"))
      (node (ref "U24") (pin "10") (pinfunction "MR_10") (pintype "input"))
      (node (ref "U25") (pin "10") (pinfunction "MR_10") (pintype "input"))
      (node (ref "U7") (pin "6") (pinfunction "~{Q}_6") (pintype "output"))
    )
    (net (code "184") (name "SCLK") (class "Default")
      (node (ref "LPC1769") (pin "13") (pinfunction "13_13") (pintype "passive"))
      (node (ref "R10") (pin "1") (pinfunction "1_1") (pintype "passive"))
      (node (ref "U22") (pin "11") (pinfunction "SHCP_11") (pintype "input"))
      (node (ref "U23") (pin "11") (pinfunction "SHCP_11") (pintype "input"))
      (node (ref "U24") (pin "11") (pinfunction "SHCP_11") (pintype "input"))
      (node (ref "U25") (pin "11") (pinfunction "SHCP_11") (pintype "input"))
      (node (ref "U7") (pin "1") (pinfunction "CLK_1") (pintype "input"))
    )
    (net (code "185") (name "VB_L") (class "Default")
      (node (ref "U13") (pin "1") (pinfunction "A_1") (pintype "input"))
      (node (ref "U30") (pin "10") (pinfunction "Q_10") (pintype "output"))
    )
    (net (code "186") (name "VGA_B") (class "Default")
      (node (ref "ADV7125") (pin "28") (pinfunction "IOB_28") (pintype "output"))
      (node (ref "J1") (pin "3") (pinfunction "BLUE_3") (pintype "passive"))
      (node (ref "R4") (pin "2") (pinfunction "2_2") (pintype "passive"))
    )
    (net (code "187") (name "VGA_G") (class "Default")
      (node (ref "ADV7125") (pin "32") (pinfunction "IOG_32") (pintype "output"))
      (node (ref "J1") (pin "2") (pinfunction "GREEN_2") (pintype "passive"))
      (node (ref "R3") (pin "2") (pinfunction "2_2") (pintype "passive"))
    )
    (net (code "188") (name "VGA_R") (class "Default")
      (node (ref "ADV7125") (pin "34") (pinfunction "IOR_34") (pintype "output"))
      (node (ref "J1") (pin "1") (pinfunction "RED_1") (pintype "passive"))
      (node (ref "R2") (pin "2") (pinfunction "2_2") (pintype "passive"))
    )
    (net (code "189") (name "VS") (class "Default")
      (node (ref "IC6") (pin "18") (pinfunction "I/O4_18") (pintype "bidirectional"))
      (node (ref "U29") (pin "14") (pinfunction "J_14") (pintype "input"))
    )
    (net (code "190") (name "VSYNC") (class "Default")
      (node (ref "J1") (pin "14") (pinfunction "VSYNC_14") (pintype "passive"))
      (node (ref "LPC1769") (pin "12") (pinfunction "12_12") (pintype "passive"))
      (node (ref "U28") (pin "3") (pinfunction "CLK_3") (pintype "input"))
      (node (ref "U29") (pin "10") (pinfunction "Q_10") (pintype "output"))
    )
    (net (code "191") (name "V_BLANK") (class "Default")
      (node (ref "IC6") (pin "19") (pinfunction "I/O5_19") (pintype "bidirectional"))
      (node (ref "U30") (pin "14") (pinfunction "J_14") (pintype "input"))
    )
    (net (code "192") (name "W_LATCH") (class "Default")
      (node (ref "U27") (pin "2") (pinfunction "A_2") (pintype "input"))
      (node (ref "U31") (pin "2") (pinfunction "A_2") (pintype "input"))
      (node (ref "U7") (pin "5") (pinfunction "Q_5") (pintype "output"))
    )
    (net (code "193") (name "unconnected-(IC6A-I{slash}O0-Pad14)") (class "Default")
      (node (ref "IC6") (pin "14") (pinfunction "I/O0_14") (pintype "bidirectional"))
    )
    (net (code "194") (name "unconnected-(IC6A-I{slash}O1-Pad15)") (class "Default")
      (node (ref "IC6") (pin "15") (pinfunction "I/O1_15") (pintype "bidirectional"))
    )
    (net (code "195") (name "unconnected-(IC6A-I{slash}O7-Pad21)") (class "Default")
      (node (ref "IC6") (pin "21") (pinfunction "I/O7_21") (pintype "bidirectional"))
    )
    (net (code "196") (name "unconnected-(IC6A-I{slash}O8-Pad22)") (class "Default")
      (node (ref "IC6") (pin "22") (pinfunction "I/O8_22") (pintype "bidirectional"))
    )
    (net (code "197") (name "unconnected-(IC6A-I{slash}O9-Pad23)") (class "Default")
      (node (ref "IC6") (pin "23") (pinfunction "I/O9_23") (pintype "bidirectional"))
    )
    (net (code "198") (name "unconnected-(IC7A-I{slash}O0-Pad14)") (class "Default")
      (node (ref "IC7") (pin "14") (pinfunction "I/O0_14") (pintype "bidirectional"))
    )
    (net (code "199") (name "unconnected-(IC7A-I{slash}O1-Pad15)") (class "Default")
      (node (ref "IC7") (pin "15") (pinfunction "I/O1_15") (pintype "bidirectional"))
    )
    (net (code "200") (name "unconnected-(IC7A-I{slash}O7-Pad21)") (class "Default")
      (node (ref "IC7") (pin "21") (pinfunction "I/O7_21") (pintype "bidirectional"))
    )
    (net (code "201") (name "unconnected-(IC7A-I{slash}O8-Pad22)") (class "Default")
      (node (ref "IC7") (pin "22") (pinfunction "I/O8_22") (pintype "bidirectional"))
    )
    (net (code "202") (name "unconnected-(IC7A-I{slash}O9-Pad23)") (class "Default")
      (node (ref "IC7") (pin "23") (pinfunction "I/O9_23") (pintype "bidirectional"))
    )
    (net (code "203") (name "unconnected-(J1-16-PadP$1)") (class "Default")
      (node (ref "J1") (pin "P$1") (pinfunction "16_P$1") (pintype "passive"))
    )
    (net (code "204") (name "unconnected-(J1-17-PadP$2)") (class "Default")
      (node (ref "J1") (pin "P$2") (pinfunction "17_P$2") (pintype "passive"))
    )
    (net (code "205") (name "unconnected-(J1-NC-Pad4)") (class "Default")
      (node (ref "J1") (pin "4") (pinfunction "NC_4") (pintype "passive"))
    )
    (net (code "206") (name "unconnected-(J1-NC-Pad9)") (class "Default")
      (node (ref "J1") (pin "9") (pinfunction "NC_9") (pintype "passive"))
    )
    (net (code "207") (name "unconnected-(J1-NC-Pad11)") (class "Default")
      (node (ref "J1") (pin "11") (pinfunction "NC_11") (pintype "passive"))
    )
    (net (code "208") (name "unconnected-(J1-SCL-Pad15)") (class "Default")
      (node (ref "J1") (pin "15") (pinfunction "SCL_15") (pintype "passive"))
    )
    (net (code "209") (name "unconnected-(J1-SDA-Pad12)") (class "Default")
      (node (ref "J1") (pin "12") (pinfunction "SDA_12") (pintype "passive"))
    )
    (net (code "210") (name "unconnected-(LPC1769-Pad1)") (class "Default")
      (node (ref "LPC1769") (pin "1") (pinfunction "1_1") (pintype "passive"))
    )
    (net (code "211") (name "unconnected-(LPC1769-Pad2)") (class "Default")
      (node (ref "LPC1769") (pin "2") (pinfunction "2_2") (pintype "passive"))
    )
    (net (code "212") (name "unconnected-(LPC1769-Pad3)") (class "Default")
      (node (ref "LPC1769") (pin "3") (pinfunction "3_3") (pintype "passive"))
    )
    (net (code "213") (name "unconnected-(LPC1769-Pad4)") (class "Default")
      (node (ref "LPC1769") (pin "4") (pinfunction "4_4") (pintype "passive"))
    )
    (net (code "214") (name "unconnected-(LPC1769-Pad5)") (class "Default")
      (node (ref "LPC1769") (pin "5") (pinfunction "5_5") (pintype "passive"))
    )
    (net (code "215") (name "unconnected-(LPC1769-Pad6)") (class "Default")
      (node (ref "LPC1769") (pin "6") (pinfunction "6_6") (pintype "passive"))
    )
    (net (code "216") (name "unconnected-(LPC1769-Pad7)") (class "Default")
      (node (ref "LPC1769") (pin "7") (pinfunction "7_7") (pintype "passive"))
    )
    (net (code "217") (name "unconnected-(LPC1769-Pad8)") (class "Default")
      (node (ref "LPC1769") (pin "8") (pinfunction "8_8") (pintype "passive"))
    )
    (net (code "218") (name "unconnected-(LPC1769-Pad9)") (class "Default")
      (node (ref "LPC1769") (pin "9") (pinfunction "9_9") (pintype "passive"))
    )
    (net (code "219") (name "unconnected-(LPC1769-Pad10)") (class "Default")
      (node (ref "LPC1769") (pin "10") (pinfunction "10_10") (pintype "passive"))
    )
    (net (code "220") (name "unconnected-(LPC1769-Pad15)") (class "Default")
      (node (ref "LPC1769") (pin "15") (pinfunction "15_15") (pintype "passive"))
    )
    (net (code "221") (name "unconnected-(LPC1769-Pad16)") (class "Default")
      (node (ref "LPC1769") (pin "16") (pinfunction "16_16") (pintype "passive"))
    )
    (net (code "222") (name "unconnected-(LPC1769-Pad17)") (class "Default")
      (node (ref "LPC1769") (pin "17") (pinfunction "17_17") (pintype "passive"))
    )
    (net (code "223") (name "unconnected-(LPC1769-Pad18)") (class "Default")
      (node (ref "LPC1769") (pin "18") (pinfunction "18_18") (pintype "passive"))
    )
    (net (code "224") (name "unconnected-(LPC1769-Pad19)") (class "Default")
      (node (ref "LPC1769") (pin "19") (pinfunction "19_19") (pintype "passive"))
    )
    (net (code "225") (name "unconnected-(LPC1769-Pad20)") (class "Default")
      (node (ref "LPC1769") (pin "20") (pinfunction "20_20") (pintype "passive"))
    )
    (net (code "226") (name "unconnected-(LPC1769-Pad21)") (class "Default")
      (node (ref "LPC1769") (pin "21") (pinfunction "21_21") (pintype "passive"))
    )
    (net (code "227") (name "unconnected-(LPC1769-Pad22)") (class "Default")
      (node (ref "LPC1769") (pin "22") (pinfunction "22_22") (pintype "passive"))
    )
    (net (code "228") (name "unconnected-(LPC1769-Pad23)") (class "Default")
      (node (ref "LPC1769") (pin "23") (pinfunction "23_23") (pintype "passive"))
    )
    (net (code "229") (name "unconnected-(LPC1769-Pad24)") (class "Default")
      (node (ref "LPC1769") (pin "24") (pinfunction "24_24") (pintype "passive"))
    )
    (net (code "230") (name "unconnected-(LPC1769-Pad25)") (class "Default")
      (node (ref "LPC1769") (pin "25") (pinfunction "25_25") (pintype "passive"))
    )
    (net (code "231") (name "unconnected-(LPC1769-Pad26)") (class "Default")
      (node (ref "LPC1769") (pin "26") (pinfunction "26_26") (pintype "passive"))
    )
    (net (code "232") (name "unconnected-(LPC1769-Pad27)") (class "Default")
      (node (ref "LPC1769") (pin "27") (pinfunction "27_27") (pintype "passive"))
    )
    (net (code "233") (name "unconnected-(LPC1769-Pad29)") (class "Default")
      (node (ref "LPC1769") (pin "29") (pinfunction "29_29") (pintype "passive"))
    )
    (net (code "234") (name "unconnected-(LPC1769-Pad30)") (class "Default")
      (node (ref "LPC1769") (pin "30") (pinfunction "30_30") (pintype "passive"))
    )
    (net (code "235") (name "unconnected-(LPC1769-Pad31)") (class "Default")
      (node (ref "LPC1769") (pin "31") (pinfunction "31_31") (pintype "passive"))
    )
    (net (code "236") (name "unconnected-(LPC1769-Pad32)") (class "Default")
      (node (ref "LPC1769") (pin "32") (pinfunction "32_32") (pintype "passive"))
    )
    (net (code "237") (name "unconnected-(LPC1769-Pad33)") (class "Default")
      (node (ref "LPC1769") (pin "33") (pinfunction "33_33") (pintype "passive"))
    )
    (net (code "238") (name "unconnected-(LPC1769-Pad34)") (class "Default")
      (node (ref "LPC1769") (pin "34") (pinfunction "34_34") (pintype "passive"))
    )
    (net (code "239") (name "unconnected-(LPC1769-Pad35)") (class "Default")
      (node (ref "LPC1769") (pin "35") (pinfunction "35_35") (pintype "passive"))
    )
    (net (code "240") (name "unconnected-(LPC1769-Pad36)") (class "Default")
      (node (ref "LPC1769") (pin "36") (pinfunction "36_36") (pintype "passive"))
    )
    (net (code "241") (name "unconnected-(LPC1769-Pad37)") (class "Default")
      (node (ref "LPC1769") (pin "37") (pinfunction "37_37") (pintype "passive"))
    )
    (net (code "242") (name "unconnected-(LPC1769-Pad38)") (class "Default")
      (node (ref "LPC1769") (pin "38") (pinfunction "38_38") (pintype "passive"))
    )
    (net (code "243") (name "unconnected-(LPC1769-Pad39)") (class "Default")
      (node (ref "LPC1769") (pin "39") (pinfunction "39_39") (pintype "passive"))
    )
    (net (code "244") (name "unconnected-(LPC1769-Pad40)") (class "Default")
      (node (ref "LPC1769") (pin "40") (pinfunction "40_40") (pintype "passive"))
    )
    (net (code "245") (name "unconnected-(LPC1769-Pad41)") (class "Default")
      (node (ref "LPC1769") (pin "41") (pinfunction "41_41") (pintype "passive"))
    )
    (net (code "246") (name "unconnected-(LPC1769-Pad42)") (class "Default")
      (node (ref "LPC1769") (pin "42") (pinfunction "42_42") (pintype "passive"))
    )
    (net (code "247") (name "unconnected-(LPC1769-Pad43)") (class "Default")
      (node (ref "LPC1769") (pin "43") (pinfunction "43_43") (pintype "passive"))
    )
    (net (code "248") (name "unconnected-(LPC1769-Pad44)") (class "Default")
      (node (ref "LPC1769") (pin "44") (pinfunction "44_44") (pintype "passive"))
    )
    (net (code "249") (name "unconnected-(LPC1769-Pad45)") (class "Default")
      (node (ref "LPC1769") (pin "45") (pinfunction "45_45") (pintype "passive"))
    )
    (net (code "250") (name "unconnected-(LPC1769-Pad46)") (class "Default")
      (node (ref "LPC1769") (pin "46") (pinfunction "46_46") (pintype "passive"))
    )
    (net (code "251") (name "unconnected-(LPC1769-Pad47)") (class "Default")
      (node (ref "LPC1769") (pin "47") (pinfunction "47_47") (pintype "passive"))
    )
    (net (code "252") (name "unconnected-(LPC1769-Pad48)") (class "Default")
      (node (ref "LPC1769") (pin "48") (pinfunction "48_48") (pintype "passive"))
    )
    (net (code "253") (name "unconnected-(LPC1769-Pad49)") (class "Default")
      (node (ref "LPC1769") (pin "49") (pinfunction "49_49") (pintype "passive"))
    )
    (net (code "254") (name "unconnected-(LPC1769-Pad50)") (class "Default")
      (node (ref "LPC1769") (pin "50") (pinfunction "50_50") (pintype "passive"))
    )
    (net (code "255") (name "unconnected-(LPC1769-Pad51)") (class "Default")
      (node (ref "LPC1769") (pin "51") (pinfunction "51_51") (pintype "passive"))
    )
    (net (code "256") (name "unconnected-(LPC1769-Pad52)") (class "Default")
      (node (ref "LPC1769") (pin "52") (pinfunction "52_52") (pintype "passive"))
    )
    (net (code "257") (name "unconnected-(LPC1769-Pad53)") (class "Default")
      (node (ref "LPC1769") (pin "53") (pinfunction "53_53") (pintype "passive"))
    )
    (net (code "258") (name "unconnected-(LPC1769-Pad55)") (class "Default")
      (node (ref "LPC1769") (pin "55") (pinfunction "55_55") (pintype "passive"))
    )
    (net (code "259") (name "unconnected-(LPC1769-Pad56)") (class "Default")
      (node (ref "LPC1769") (pin "56") (pinfunction "56_56") (pintype "passive"))
    )
    (net (code "260") (name "unconnected-(LPC1769-Pad57)") (class "Default")
      (node (ref "LPC1769") (pin "57") (pinfunction "57_57") (pintype "passive"))
    )
    (net (code "261") (name "unconnected-(LPC1769-Pad58)") (class "Default")
      (node (ref "LPC1769") (pin "58") (pinfunction "58_58") (pintype "passive"))
    )
    (net (code "262") (name "unconnected-(LPC1769-Pad59)") (class "Default")
      (node (ref "LPC1769") (pin "59") (pinfunction "59_59") (pintype "passive"))
    )
    (net (code "263") (name "unconnected-(LPC1769-Pad60)") (class "Default")
      (node (ref "LPC1769") (pin "60") (pinfunction "60_60") (pintype "passive"))
    )
    (net (code "264") (name "unconnected-(LPC1769-Pad61)") (class "Default")
      (node (ref "LPC1769") (pin "61") (pinfunction "61_61") (pintype "passive"))
    )
    (net (code "265") (name "unconnected-(LPC1769-Pad62)") (class "Default")
      (node (ref "LPC1769") (pin "62") (pinfunction "62_62") (pintype "passive"))
    )
    (net (code "266") (name "unconnected-(LPC1769-Pad63)") (class "Default")
      (node (ref "LPC1769") (pin "63") (pinfunction "63_63") (pintype "passive"))
    )
    (net (code "267") (name "unconnected-(LPC1769-Pad64)") (class "Default")
      (node (ref "LPC1769") (pin "64") (pinfunction "64_64") (pintype "passive"))
    )
    (net (code "268") (name "unconnected-(LPC1769-Pad65)") (class "Default")
      (node (ref "LPC1769") (pin "65") (pinfunction "65_65") (pintype "passive"))
    )
    (net (code "269") (name "unconnected-(LPC1769-Pad66)") (class "Default")
      (node (ref "LPC1769") (pin "66") (pinfunction "66_66") (pintype "passive"))
    )
    (net (code "270") (name "unconnected-(LPC1769-Pad67)") (class "Default")
      (node (ref "LPC1769") (pin "67") (pinfunction "67_67") (pintype "passive"))
    )
    (net (code "271") (name "unconnected-(LPC1769-Pad68)") (class "Default")
      (node (ref "LPC1769") (pin "68") (pinfunction "68_68") (pintype "passive"))
    )
    (net (code "272") (name "unconnected-(LPC1769-Pad69)") (class "Default")
      (node (ref "LPC1769") (pin "69") (pinfunction "69_69") (pintype "passive"))
    )
    (net (code "273") (name "unconnected-(LPC1769-Pad70)") (class "Default")
      (node (ref "LPC1769") (pin "70") (pinfunction "70_70") (pintype "passive"))
    )
    (net (code "274") (name "unconnected-(LPC1769-Pad71)") (class "Default")
      (node (ref "LPC1769") (pin "71") (pinfunction "71_71") (pintype "passive"))
    )
    (net (code "275") (name "unconnected-(LPC1769-Pad72)") (class "Default")
      (node (ref "LPC1769") (pin "72") (pinfunction "72_72") (pintype "passive"))
    )
    (net (code "276") (name "unconnected-(LPC1769-Pad73)") (class "Default")
      (node (ref "LPC1769") (pin "73") (pinfunction "73_73") (pintype "passive"))
    )
    (net (code "277") (name "unconnected-(U7B-Q-Pad9)") (class "Default")
      (node (ref "U7") (pin "9") (pinfunction "Q_9") (pintype "output"))
    )
    (net (code "278") (name "unconnected-(U7B-~{Q}-Pad7)") (class "Default")
      (node (ref "U7") (pin "7") (pinfunction "~{Q}_7") (pintype "output"))
    )
    (net (code "279") (name "unconnected-(U16A-TC-Pad15)") (class "Default")
      (node (ref "U16") (pin "15") (pinfunction "TC_15") (pintype "output"))
    )
    (net (code "280") (name "unconnected-(U18A-TC-Pad15)") (class "Default")
      (node (ref "U18") (pin "15") (pinfunction "TC_15") (pintype "output"))
    )
    (net (code "281") (name "unconnected-(U21A-Q2-Pad12)") (class "Default")
      (node (ref "U21") (pin "12") (pinfunction "Q2_12") (pintype "output"))
    )
    (net (code "282") (name "unconnected-(U21A-Q3-Pad11)") (class "Default")
      (node (ref "U21") (pin "11") (pinfunction "Q3_11") (pintype "output"))
    )
    (net (code "283") (name "unconnected-(U21A-TC-Pad15)") (class "Default")
      (node (ref "U21") (pin "15") (pinfunction "TC_15") (pintype "output"))
    )
    (net (code "284") (name "unconnected-(U25A-Q4-Pad4)") (class "Default")
      (node (ref "U25") (pin "4") (pinfunction "Q4_4") (pintype "output"))
    )
    (net (code "285") (name "unconnected-(U25A-Q5-Pad5)") (class "Default")
      (node (ref "U25") (pin "5") (pinfunction "Q5_5") (pintype "output"))
    )
    (net (code "286") (name "unconnected-(U25A-Q6-Pad6)") (class "Default")
      (node (ref "U25") (pin "6") (pinfunction "Q6_6") (pintype "output"))
    )
    (net (code "287") (name "unconnected-(U25A-Q7-Pad7)") (class "Default")
      (node (ref "U25") (pin "7") (pinfunction "Q7_7") (pintype "output"))
    )
    (net (code "288") (name "unconnected-(U28B-Q-Pad9)") (class "Default")
      (node (ref "U28") (pin "9") (pinfunction "Q_9") (pintype "output"))
    )
    (net (code "289") (name "unconnected-(U28B-~{Q}-Pad8)") (class "Default")
      (node (ref "U28") (pin "8") (pinfunction "~{Q}_8") (pintype "output"))
    )
    (net (code "290") (name "unconnected-(U29A-~{Q}-Pad7)") (class "Default")
      (node (ref "U29") (pin "7") (pinfunction "~{Q}_7") (pintype "output"))
    )
    (net (code "291") (name "unconnected-(U29B-~{Q}-Pad9)") (class "Default")
      (node (ref "U29") (pin "9") (pinfunction "~{Q}_9") (pintype "output"))
    )
    (net (code "292") (name "unconnected-(U30A-~{Q}-Pad7)") (class "Default")
      (node (ref "U30") (pin "7") (pinfunction "~{Q}_7") (pintype "output"))
    )
    (net (code "293") (name "unconnected-(U30B-~{Q}-Pad9)") (class "Default")
      (node (ref "U30") (pin "9") (pinfunction "~{Q}_9") (pintype "output"))
    )
    (net (code "294") (name "unconnected-(X1-TS-Pad1)") (class "Default")
      (node (ref "X1") (pin "1") (pinfunction "TS_1") (pintype "passive"))
    )
    (net (code "295") (name "~{BLANK}") (class "Default")
      (node (ref "ADV7125") (pin "11") (pinfunction "~{BLANK}_11") (pintype "input"))
      (node (ref "U13") (pin "4") (pinfunction "Y_4") (pintype "output"))
    )
    (net (code "296") (name "~{HS}") (class "Default")
      (node (ref "IC7") (pin "19") (pinfunction "I/O5_19") (pintype "bidirectional"))
      (node (ref "U29") (pin "3") (pinfunction "K_3") (pintype "input"))
    )
    (net (code "297") (name "~{H_BLANK}") (class "Default")
      (node (ref "IC7") (pin "18") (pinfunction "I/O4_18") (pintype "bidirectional"))
      (node (ref "U30") (pin "3") (pinfunction "K_3") (pintype "input"))
    )
    (net (code "298") (name "~{H_EOL}") (class "Default")
      (node (ref "IC7") (pin "16") (pinfunction "I/O2_16") (pintype "bidirectional"))
      (node (ref "U17") (pin "1") (pinfunction "MR_1") (pintype "input"))
      (node (ref "U18") (pin "1") (pinfunction "MR_1") (pintype "input"))
      (node (ref "U19") (pin "2") (pinfunction "CLK_2") (pintype "input"))
      (node (ref "U20") (pin "2") (pinfunction "CLK_2") (pintype "input"))
      (node (ref "U21") (pin "2") (pinfunction "CLK_2") (pintype "input"))
      (node (ref "U6") (pin "1") (pinfunction "MR_1") (pintype "input"))
    )
    (net (code "299") (name "~{M1_WE}") (class "Default")
      (node (ref "SRAM1") (pin "15") (pinfunction "WE_15") (pintype "input"))
      (node (ref "U27") (pin "4") (pinfunction "Y_4") (pintype "output"))
    )
    (net (code "300") (name "~{M2_WE}") (class "Default")
      (node (ref "SRAM2") (pin "15") (pinfunction "WE_15") (pintype "input"))
      (node (ref "U31") (pin "4") (pinfunction "Y_4") (pintype "output"))
    )
    (net (code "301") (name "~{VS}") (class "Default")
      (node (ref "IC6") (pin "17") (pinfunction "I/O3_17") (pintype "bidirectional"))
      (node (ref "U29") (pin "13") (pinfunction "K_13") (pintype "input"))
    )
    (net (code "302") (name "~{V_BLANK}") (class "Default")
      (node (ref "IC6") (pin "20") (pinfunction "I/O6_20") (pintype "bidirectional"))
      (node (ref "U30") (pin "13") (pinfunction "K_13") (pintype "input"))
    )
    (net (code "303") (name "~{V_EOF}") (class "Default")
      (node (ref "IC6") (pin "16") (pinfunction "I/O2_16") (pintype "bidirectional"))
      (node (ref "U12") (pin "1") (pinfunction "MR_1") (pintype "input"))
      (node (ref "U14") (pin "1") (pinfunction "MR_1") (pintype "input"))
      (node (ref "U15") (pin "1") (pinfunction "MR_1") (pintype "input"))
      (node (ref "U16") (pin "1") (pinfunction "MR_1") (pintype "input"))
      (node (ref "U19") (pin "1") (pinfunction "MR_1") (pintype "input"))
      (node (ref "U20") (pin "1") (pinfunction "MR_1") (pintype "input"))
      (node (ref "U21") (pin "1") (pinfunction "MR_1") (pintype "input"))
      (node (ref "U5") (pin "1") (pinfunction "MR_1") (pintype "input"))
    )
  )
)
